# PCB_Official.net
KiCad netlist of a schematic drawn in EAGLE
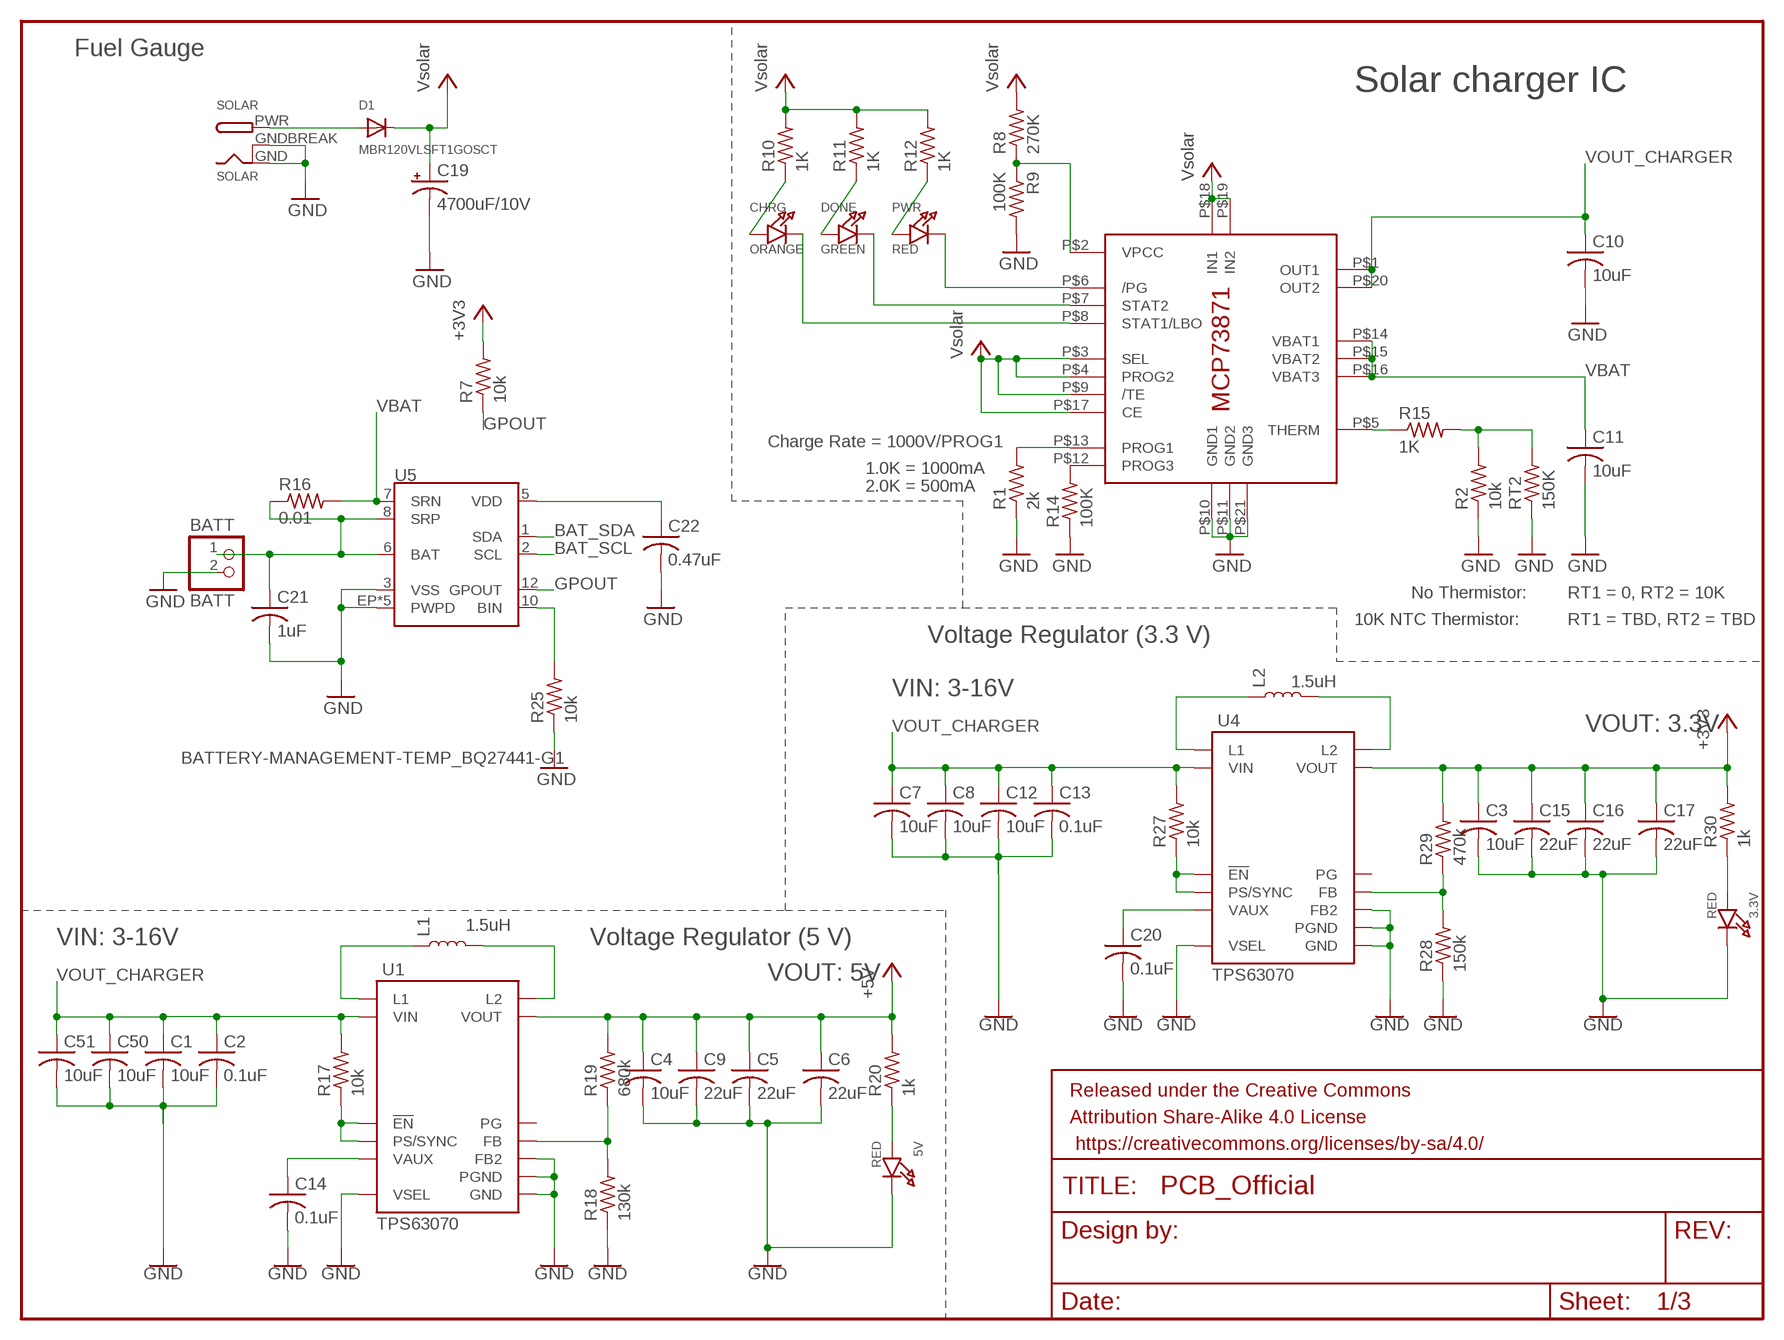
[diagram p0: schematic, sheet 1]
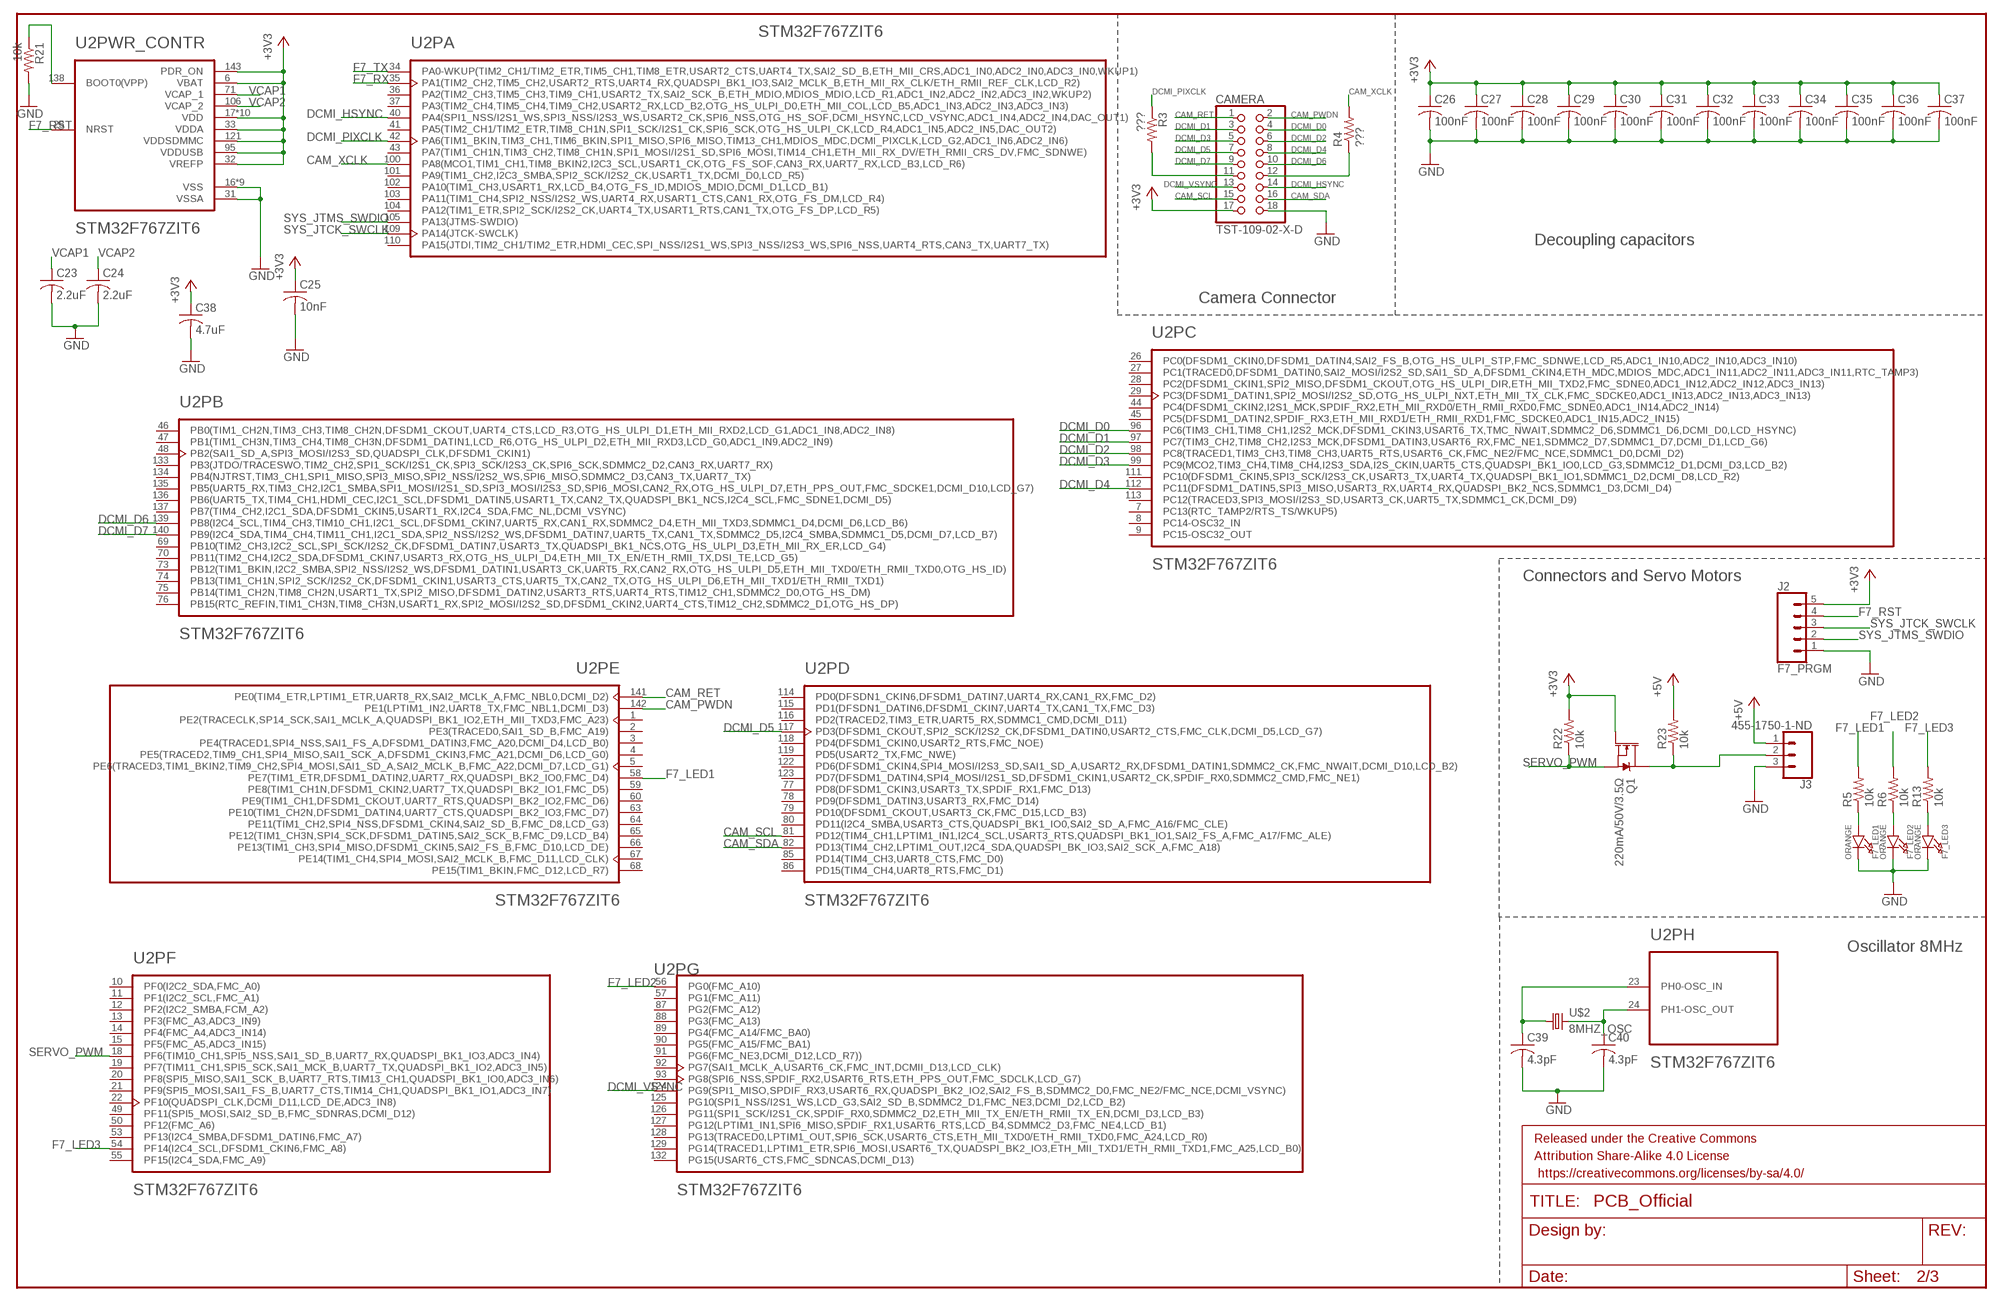
[diagram p1: schematic, sheet 2]
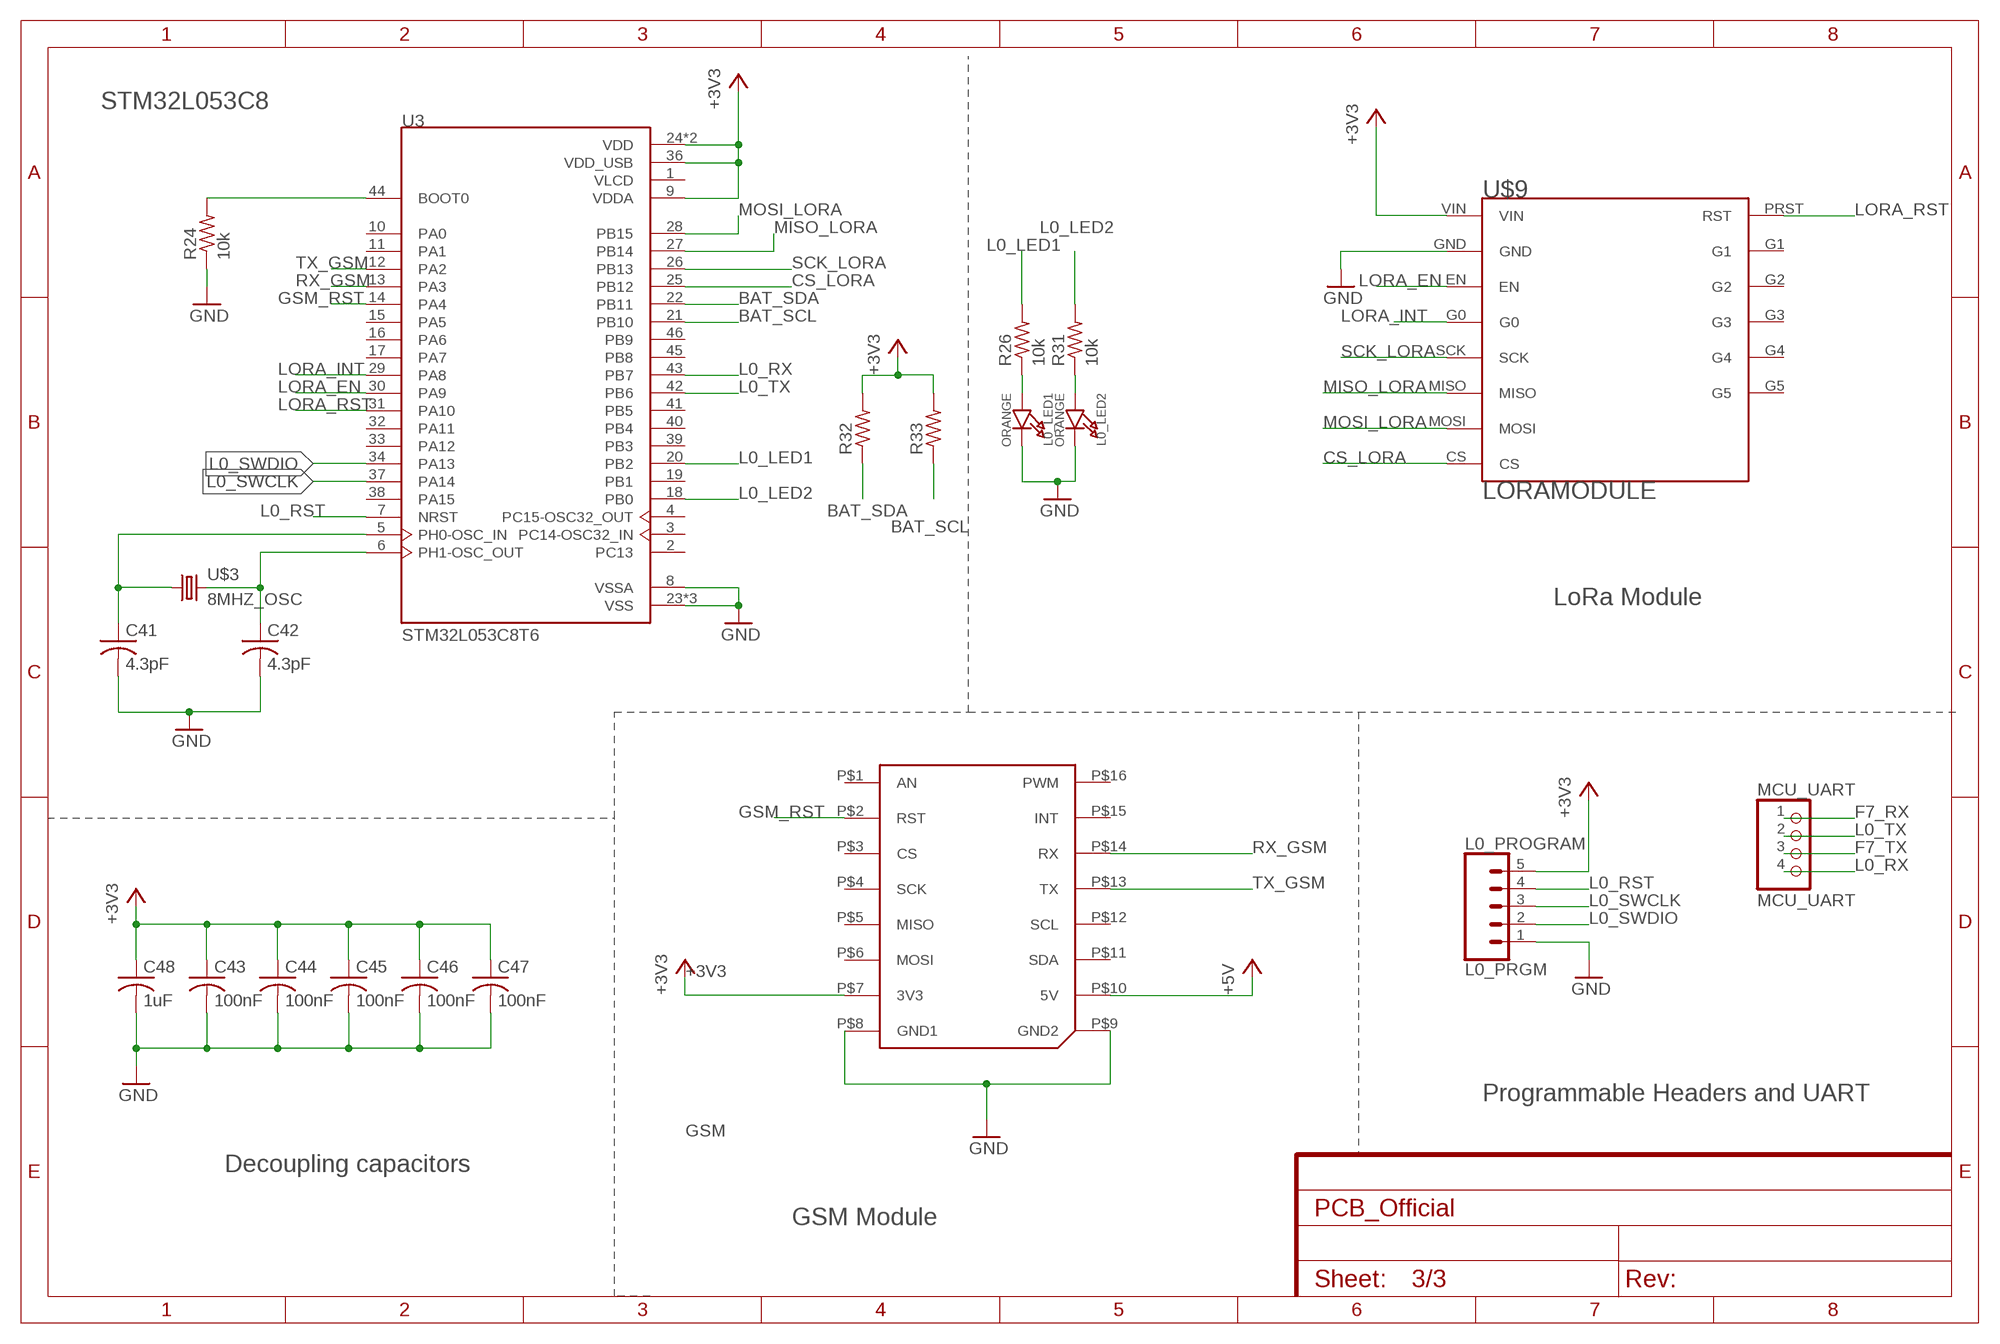
[diagram p2: schematic, sheet 3]

(export (version "E")
  (design (tool "Eeschema 10.0.6"))
  (components
    (comp (ref "C23")
      (value "2.2uF")
      (footprint "eagle-import:C0805")
      (libsource (lib "eagle-import") (part "rcl_334_C-USC0805"))
    )
    (comp (ref "C24")
      (value "2.2uF")
      (footprint "eagle-import:C0805")
      (libsource (lib "eagle-import") (part "rcl_334_C-USC0805"))
    )
    (comp (ref "C25")
      (value "10nF")
      (footprint "eagle-import:C0805")
      (libsource (lib "eagle-import") (part "rcl_334_C-USC0805"))
    )
    (comp (ref "C26")
      (value "100nF")
      (footprint "eagle-import:C0805")
      (libsource (lib "eagle-import") (part "rcl_334_C-USC0805"))
    )
    (comp (ref "C27")
      (value "100nF")
      (footprint "eagle-import:C0805")
      (libsource (lib "eagle-import") (part "rcl_334_C-USC0805"))
    )
    (comp (ref "C28")
      (value "100nF")
      (footprint "eagle-import:C0805")
      (libsource (lib "eagle-import") (part "rcl_334_C-USC0805"))
    )
    (comp (ref "C29")
      (value "100nF")
      (footprint "eagle-import:C0805")
      (libsource (lib "eagle-import") (part "rcl_334_C-USC0805"))
    )
    (comp (ref "C30")
      (value "100nF")
      (footprint "eagle-import:C0805")
      (libsource (lib "eagle-import") (part "rcl_334_C-USC0805"))
    )
    (comp (ref "C31")
      (value "100nF")
      (footprint "eagle-import:C0805")
      (libsource (lib "eagle-import") (part "rcl_334_C-USC0805"))
    )
    (comp (ref "C32")
      (value "100nF")
      (footprint "eagle-import:C0805")
      (libsource (lib "eagle-import") (part "rcl_334_C-USC0805"))
    )
    (comp (ref "C33")
      (value "100nF")
      (footprint "eagle-import:C0805")
      (libsource (lib "eagle-import") (part "rcl_334_C-USC0805"))
    )
    (comp (ref "C34")
      (value "100nF")
      (footprint "eagle-import:C0805")
      (libsource (lib "eagle-import") (part "rcl_334_C-USC0805"))
    )
    (comp (ref "C35")
      (value "100nF")
      (footprint "eagle-import:C0805")
      (libsource (lib "eagle-import") (part "rcl_334_C-USC0805"))
    )
    (comp (ref "C36")
      (value "100nF")
      (footprint "eagle-import:C0805")
      (libsource (lib "eagle-import") (part "rcl_334_C-USC0805"))
    )
    (comp (ref "C37")
      (value "100nF")
      (footprint "eagle-import:C0805")
      (libsource (lib "eagle-import") (part "rcl_334_C-USC0805"))
    )
    (comp (ref "C38")
      (value "4.7uF")
      (footprint "eagle-import:C0805")
      (libsource (lib "eagle-import") (part "rcl_334_C-USC0805"))
    )
    (comp (ref "C39")
      (value "4.3pF")
      (footprint "eagle-import:C0805")
      (libsource (lib "eagle-import") (part "rcl_334_C-USC0805"))
    )
    (comp (ref "C40")
      (value "4.3pF")
      (footprint "eagle-import:C0805")
      (libsource (lib "eagle-import") (part "rcl_334_C-USC0805"))
    )
    (comp (ref "CAMERA")
      (value "TST-109-02-X-D")
      (footprint "eagle-import:TST-109-02-X-D")
      (libsource (lib "eagle-import") (part "TST-109-02-X-D"))
    )
    (comp (ref "F7_LED1")
      (value "ORANGE")
      (footprint "eagle-import:CHIPLED_0805_NOOUTLINE")
      (libsource (lib "eagle-import") (part "LED0805_NOOUTLINE"))
    )
    (comp (ref "F7_LED2")
      (value "ORANGE")
      (footprint "eagle-import:CHIPLED_0805_NOOUTLINE")
      (libsource (lib "eagle-import") (part "LED0805_NOOUTLINE"))
    )
    (comp (ref "F7_LED3")
      (value "ORANGE")
      (footprint "eagle-import:CHIPLED_0805_NOOUTLINE")
      (libsource (lib "eagle-import") (part "LED0805_NOOUTLINE"))
    )
    (comp (ref "FRAME3")
      (value "FRAME-LEDGER")
      (footprint "eagle-import:CREATIVE_COMMONS")
      (libsource (lib "eagle-import") (part "FRAME-LEDGER"))
    )
    (comp (ref "J2")
      (value "F7_PRGM")
      (footprint "eagle-import:1X05")
      (libsource (lib "eagle-import") (part "CONN_05"))
    )
    (comp (ref "J3")
      (value "455-1750-1-ND")
      (footprint "eagle-import:1X03")
      (libsource (lib "eagle-import") (part "CONN_03"))
    )
    (comp (ref "Q1")
      (value "220mA/50V/3.5Ω")
      (footprint "eagle-import:SOT23-3")
      (libsource (lib "eagle-import") (part "MOSFET-NCH-BSS138"))
    )
    (comp (ref "R3")
      (value "???")
      (footprint "eagle-import:R0805")
      (libsource (lib "eagle-import") (part "rcl_334_R-US_R0805"))
    )
    (comp (ref "R4")
      (value "???")
      (footprint "eagle-import:R0805")
      (libsource (lib "eagle-import") (part "rcl_334_R-US_R0805"))
    )
    (comp (ref "R5")
      (value "10k")
      (footprint "eagle-import:R0805")
      (libsource (lib "eagle-import") (part "rcl_334_R-US_R0805"))
    )
    (comp (ref "R6")
      (value "10k")
      (footprint "eagle-import:R0805")
      (libsource (lib "eagle-import") (part "rcl_334_R-US_R0805"))
    )
    (comp (ref "R13")
      (value "10k")
      (footprint "eagle-import:R0805")
      (libsource (lib "eagle-import") (part "rcl_334_R-US_R0805"))
    )
    (comp (ref "R21")
      (value "10k")
      (footprint "eagle-import:R0805")
      (libsource (lib "eagle-import") (part "rcl_334_R-US_R0805"))
    )
    (comp (ref "R22")
      (value "10k")
      (footprint "eagle-import:R0805")
      (libsource (lib "eagle-import") (part "rcl_334_R-US_R0805"))
    )
    (comp (ref "R23")
      (value "10k")
      (footprint "eagle-import:R0805")
      (libsource (lib "eagle-import") (part "rcl_334_R-US_R0805"))
    )
    (comp (ref "U$2")
      (value "8MHZ_OSC")
      (footprint "eagle-import:8MHZ_OSC")
      (libsource (lib "eagle-import") (part "8MHZ_OSC"))
    )
    (comp (ref "U2")
      (value "STM32F767ZIT6")
      (footprint "eagle-import:QFP50P2200X2200X160-144N")
      (fields (field (name "DIGI-KEY_PART_NUMBER") "497-16521-ND") (field (name "MF") "STMicroelectronics"))
      (libsource (lib "eagle-import") (part "STM32F767ZIT6"))
    )
    (comp (ref "C41")
      (value "4.3pF")
      (footprint "eagle-import:C0805")
      (libsource (lib "eagle-import") (part "rcl_334_C-USC0805"))
    )
    (comp (ref "C42")
      (value "4.3pF")
      (footprint "eagle-import:C0805")
      (libsource (lib "eagle-import") (part "rcl_334_C-USC0805"))
    )
    (comp (ref "C43")
      (value "100nF")
      (footprint "eagle-import:C0805")
      (libsource (lib "eagle-import") (part "rcl_334_C-USC0805"))
    )
    (comp (ref "C44")
      (value "100nF")
      (footprint "eagle-import:C0805")
      (libsource (lib "eagle-import") (part "rcl_334_C-USC0805"))
    )
    (comp (ref "C45")
      (value "100nF")
      (footprint "eagle-import:C0805")
      (libsource (lib "eagle-import") (part "rcl_334_C-USC0805"))
    )
    (comp (ref "C46")
      (value "100nF")
      (footprint "eagle-import:C0805")
      (libsource (lib "eagle-import") (part "rcl_334_C-USC0805"))
    )
    (comp (ref "C47")
      (value "100nF")
      (footprint "eagle-import:C0805")
      (libsource (lib "eagle-import") (part "rcl_334_C-USC0805"))
    )
    (comp (ref "C48")
      (value "1uF")
      (footprint "eagle-import:C0805")
      (libsource (lib "eagle-import") (part "rcl_334_C-USC0805"))
    )
    (comp (ref "L0_LED1")
      (value "ORANGE")
      (footprint "eagle-import:CHIPLED_0805_NOOUTLINE")
      (libsource (lib "eagle-import") (part "LED0805_NOOUTLINE"))
    )
    (comp (ref "L0_LED2")
      (value "ORANGE")
      (footprint "eagle-import:CHIPLED_0805_NOOUTLINE")
      (libsource (lib "eagle-import") (part "LED0805_NOOUTLINE"))
    )
    (comp (ref "L0_PROGRAM")
      (value "L0_PRGM")
      (footprint "eagle-import:1X05")
      (libsource (lib "eagle-import") (part "CONN_05"))
    )
    (comp (ref "MCU_UART")
      (value "MCU_UART")
      (footprint "eagle-import:1X04")
      (libsource (lib "eagle-import") (part "PINHD-1X4"))
    )
    (comp (ref "R24")
      (value "10k")
      (footprint "eagle-import:R0805")
      (libsource (lib "eagle-import") (part "rcl_334_R-US_R0805"))
    )
    (comp (ref "R26")
      (value "10k")
      (footprint "eagle-import:R0805")
      (libsource (lib "eagle-import") (part "rcl_334_R-US_R0805"))
    )
    (comp (ref "R31")
      (value "10k")
      (footprint "eagle-import:R0805")
      (libsource (lib "eagle-import") (part "rcl_334_R-US_R0805"))
    )
    (comp (ref "R32")
      (value "R-US_R0805")
      (footprint "eagle-import:R0805")
      (libsource (lib "eagle-import") (part "rcl_334_R-US_R0805"))
    )
    (comp (ref "R33")
      (value "R-US_R0805")
      (footprint "eagle-import:R0805")
      (libsource (lib "eagle-import") (part "rcl_334_R-US_R0805"))
    )
    (comp (ref "U$1")
      (value "MIKROE_CLICKLARGE")
      (footprint "eagle-import:MIKROE_BUS_LARGE")
      (libsource (lib "eagle-import") (part "MIKROE_CLICKLARGE"))
    )
    (comp (ref "U$3")
      (value "8MHZ_OSC")
      (footprint "eagle-import:8MHZ_OSC")
      (libsource (lib "eagle-import") (part "8MHZ_OSC"))
    )
    (comp (ref "U$9")
      (value "LORAMODULE")
      (footprint "eagle-import:LORAMODULE")
      (libsource (lib "eagle-import") (part "LORAMODULE"))
    )
    (comp (ref "U3")
      (value "STM32L053C8T6")
      (footprint "eagle-import:QFP50P900X900X160-48N")
      (fields (field (name "DIGI-KEY_PART_NUMBER") "497-14906-ND") (field (name "MF") "STMicroelectronics"))
      (libsource (lib "eagle-import") (part "STM32L053C8T6"))
    )
    (comp (ref "3.3V")
      (value "RED")
      (footprint "eagle-import:CHIPLED_0805_NOOUTLINE")
      (libsource (lib "eagle-import") (part "LED0805_NOOUTLINE"))
    )
    (comp (ref "5V")
      (value "RED")
      (footprint "eagle-import:CHIPLED_0805_NOOUTLINE")
      (libsource (lib "eagle-import") (part "LED0805_NOOUTLINE"))
    )
    (comp (ref "BATT")
      (value "BATT")
      (footprint "eagle-import:JST-PH-2-SMT-RA")
      (libsource (lib "eagle-import") (part "JST_2PIN-SMT-RA"))
    )
    (comp (ref "C1")
      (value "10uF")
      (footprint "eagle-import:C0805")
      (libsource (lib "eagle-import") (part "C-USC0805"))
    )
    (comp (ref "C2")
      (value "0.1uF")
      (footprint "eagle-import:C0805")
      (libsource (lib "eagle-import") (part "C-USC0805"))
    )
    (comp (ref "C3")
      (value "10uF")
      (footprint "eagle-import:C0603")
      (libsource (lib "eagle-import") (part "rcl_334_C-USC0603"))
    )
    (comp (ref "C4")
      (value "10uF")
      (footprint "eagle-import:C0603")
      (libsource (lib "eagle-import") (part "rcl_334_C-USC0603"))
    )
    (comp (ref "C5")
      (value "22uF")
      (footprint "eagle-import:C0805")
      (libsource (lib "eagle-import") (part "C-USC0805"))
    )
    (comp (ref "C6")
      (value "22uF")
      (footprint "eagle-import:C0805")
      (libsource (lib "eagle-import") (part "C-USC0805"))
    )
    (comp (ref "C7")
      (value "10uF")
      (footprint "eagle-import:C0603")
      (libsource (lib "eagle-import") (part "rcl_334_C-USC0603"))
    )
    (comp (ref "C8")
      (value "10uF")
      (footprint "eagle-import:C0805")
      (libsource (lib "eagle-import") (part "C-USC0805"))
    )
    (comp (ref "C9")
      (value "22uF")
      (footprint "eagle-import:C0805")
      (libsource (lib "eagle-import") (part "C-USC0805"))
    )
    (comp (ref "C10")
      (value "10uF")
      (footprint "eagle-import:C0805K")
      (libsource (lib "eagle-import") (part "C-USC0805K"))
    )
    (comp (ref "C11")
      (value "10uF")
      (footprint "eagle-import:C0805K")
      (libsource (lib "eagle-import") (part "C-USC0805K"))
    )
    (comp (ref "C12")
      (value "10uF")
      (footprint "eagle-import:C0805")
      (libsource (lib "eagle-import") (part "C-USC0805"))
    )
    (comp (ref "C13")
      (value "0.1uF")
      (footprint "eagle-import:C0805")
      (libsource (lib "eagle-import") (part "C-USC0805"))
    )
    (comp (ref "C14")
      (value "0.1uF")
      (footprint "eagle-import:C0603")
      (libsource (lib "eagle-import") (part "rcl_334_C-USC0603"))
    )
    (comp (ref "C15")
      (value "22uF")
      (footprint "eagle-import:C0805")
      (libsource (lib "eagle-import") (part "C-USC0805"))
    )
    (comp (ref "C16")
      (value "22uF")
      (footprint "eagle-import:C0805")
      (libsource (lib "eagle-import") (part "C-USC0805"))
    )
    (comp (ref "C17")
      (value "22uF")
      (footprint "eagle-import:C0805")
      (libsource (lib "eagle-import") (part "C-USC0805"))
    )
    (comp (ref "C19")
      (value "4700uF/10V")
      (footprint "eagle-import:ADAFRUIT_E5-13")
      (libsource (lib "eagle-import") (part "ADAFRUIT_CPOL-USE5-13"))
    )
    (comp (ref "C20")
      (value "0.1uF")
      (footprint "eagle-import:C0603")
      (libsource (lib "eagle-import") (part "rcl_334_C-USC0603"))
    )
    (comp (ref "C21")
      (value "1uF")
      (footprint "eagle-import:C0805")
      (libsource (lib "eagle-import") (part "rcl_334_C-USC0805"))
    )
    (comp (ref "C22")
      (value "0.47uF")
      (footprint "eagle-import:C0805")
      (libsource (lib "eagle-import") (part "rcl_334_C-USC0805"))
    )
    (comp (ref "C50")
      (value "10uF")
      (footprint "eagle-import:C0805")
      (libsource (lib "eagle-import") (part "C-USC0805"))
    )
    (comp (ref "C51")
      (value "10uF")
      (footprint "eagle-import:C0603")
      (libsource (lib "eagle-import") (part "rcl_334_C-USC0603"))
    )
    (comp (ref "CHRG")
      (value "ORANGE")
      (footprint "eagle-import:CHIPLED_0805_NOOUTLINE")
      (libsource (lib "eagle-import") (part "LED0805_NOOUTLINE"))
    )
    (comp (ref "D1")
      (value "MBR120VLSFT1GOSCT")
      (footprint "eagle-import:MICROBUILDER_SOD-123")
      (libsource (lib "eagle-import") (part "MICROBUILDER_DIODESOD-123"))
    )
    (comp (ref "DONE")
      (value "GREEN")
      (footprint "eagle-import:CHIPLED_0805_NOOUTLINE")
      (libsource (lib "eagle-import") (part "LED0805_NOOUTLINE"))
    )
    (comp (ref "FRAME2")
      (value "FRAME-LETTERNO_PACKAGE")
      (footprint "eagle-import:DUMMY")
      (fields (field (name "DESIGNER") "Nobody"))
      (libsource (lib "eagle-import") (part "FRAME-LETTERNO_PACKAGE"))
    )
    (comp (ref "IC1")
      (value "MCP73871")
      (footprint "eagle-import:QFN20_4MM")
      (libsource (lib "eagle-import") (part "MCP73871"))
    )
    (comp (ref "L1")
      (value "1.5uH")
      (footprint "eagle-import:XFL4020")
      (libsource (lib "eagle-import") (part "INDUCTOR-XFL40201.5UH"))
    )
    (comp (ref "L2")
      (value "1.5uH")
      (footprint "eagle-import:XFL4020")
      (libsource (lib "eagle-import") (part "INDUCTOR-XFL40201.5UH"))
    )
    (comp (ref "PWR")
      (value "RED")
      (footprint "eagle-import:CHIPLED_0805_NOOUTLINE")
      (libsource (lib "eagle-import") (part "LED0805_NOOUTLINE"))
    )
    (comp (ref "R1")
      (value "2k")
      (footprint "eagle-import:R0805")
      (libsource (lib "eagle-import") (part "adafruit_420_R-US_R0805"))
    )
    (comp (ref "R2")
      (value "10k")
      (footprint "eagle-import:R0805")
      (libsource (lib "eagle-import") (part "adafruit_420_R-US_R0805"))
    )
    (comp (ref "R7")
      (value "10k")
      (footprint "eagle-import:R0805")
      (libsource (lib "eagle-import") (part "adafruit_420_R-US_R0805"))
    )
    (comp (ref "R8")
      (value "270K")
      (footprint "eagle-import:R0805")
      (libsource (lib "eagle-import") (part "R-US_R0805"))
    )
    (comp (ref "R9")
      (value "100K")
      (footprint "eagle-import:R0805")
      (libsource (lib "eagle-import") (part "R-US_R0805"))
    )
    (comp (ref "R10")
      (value "1K")
      (footprint "eagle-import:R0805")
      (libsource (lib "eagle-import") (part "R-US_R0805"))
    )
    (comp (ref "R11")
      (value "1K")
      (footprint "eagle-import:R0805")
      (libsource (lib "eagle-import") (part "R-US_R0805"))
    )
    (comp (ref "R12")
      (value "1K")
      (footprint "eagle-import:R0805")
      (libsource (lib "eagle-import") (part "R-US_R0805"))
    )
    (comp (ref "R14")
      (value "100K")
      (footprint "eagle-import:R0805")
      (libsource (lib "eagle-import") (part "R-US_R0805"))
    )
    (comp (ref "R15")
      (value "1K")
      (footprint "eagle-import:M0805")
      (libsource (lib "eagle-import") (part "R-US_M0805"))
    )
    (comp (ref "R16")
      (value "0.01")
      (footprint "eagle-import:R0805")
      (libsource (lib "eagle-import") (part "rcl_334_R-US_R0805"))
    )
    (comp (ref "R17")
      (value "10k")
      (footprint "eagle-import:R0603")
      (libsource (lib "eagle-import") (part "rcl_334_R-US_R0603"))
    )
    (comp (ref "R18")
      (value "130k")
      (footprint "eagle-import:R0603")
      (libsource (lib "eagle-import") (part "rcl_334_R-US_R0603"))
    )
    (comp (ref "R19")
      (value "680k")
      (footprint "eagle-import:R0603")
      (libsource (lib "eagle-import") (part "rcl_334_R-US_R0603"))
    )
    (comp (ref "R20")
      (value "1k")
      (footprint "eagle-import:R0603")
      (libsource (lib "eagle-import") (part "rcl_334_R-US_R0603"))
    )
    (comp (ref "R25")
      (value "10k")
      (footprint "eagle-import:R0805")
      (libsource (lib "eagle-import") (part "adafruit_420_R-US_R0805"))
    )
    (comp (ref "R27")
      (value "10k")
      (footprint "eagle-import:R0603")
      (libsource (lib "eagle-import") (part "rcl_334_R-US_R0603"))
    )
    (comp (ref "R28")
      (value "150k")
      (footprint "eagle-import:R0603")
      (libsource (lib "eagle-import") (part "rcl_334_R-US_R0603"))
    )
    (comp (ref "R29")
      (value "470k")
      (footprint "eagle-import:R0603")
      (libsource (lib "eagle-import") (part "rcl_334_R-US_R0603"))
    )
    (comp (ref "R30")
      (value "1k")
      (footprint "eagle-import:R0603")
      (libsource (lib "eagle-import") (part "rcl_334_R-US_R0603"))
    )
    (comp (ref "RT2")
      (value "150K")
      (footprint "eagle-import:M0805")
      (libsource (lib "eagle-import") (part "R-US_M0805"))
    )
    (comp (ref "SOLAR")
      (value "SOLAR")
      (footprint "eagle-import:DCJACK_2MM_PTH")
      (libsource (lib "eagle-import") (part "DCBARRELPTH"))
    )
    (comp (ref "U1")
      (value "TPS63070")
      (footprint "eagle-import:VQFN-15-HR(3X2.5)")
      (libsource (lib "eagle-import") (part "TPS63070"))
    )
    (comp (ref "U4")
      (value "TPS63070")
      (footprint "eagle-import:VQFN-15-HR(3X2.5)")
      (libsource (lib "eagle-import") (part "TPS63070"))
    )
    (comp (ref "U5")
      (value "BATTERY-MANAGEMENT-TEMP_BQ27441-G1")
      (footprint "eagle-import:BATTERY-MANAGEMENT-TEMP_PDSO-N12")
      (libsource (lib "eagle-import") (part "BATTERY-MANAGEMENT-TEMP_BQ27441-G1"))
    )
  )
  (nets
    (net (code "1") (name "+3V3") (class "Default")
      (node (ref "C15") (pin "1") (pinfunction "1_1") (pintype "passive"))
      (node (ref "C16") (pin "1") (pinfunction "1_1") (pintype "passive"))
      (node (ref "C17") (pin "1") (pinfunction "1_1") (pintype "passive"))
      (node (ref "C25") (pin "1") (pinfunction "1_1") (pintype "passive"))
      (node (ref "C26") (pin "1") (pinfunction "1_1") (pintype "passive"))
      (node (ref "C27") (pin "1") (pinfunction "1_1") (pintype "passive"))
      (node (ref "C28") (pin "1") (pinfunction "1_1") (pintype "passive"))
      (node (ref "C29") (pin "1") (pinfunction "1_1") (pintype "passive"))
      (node (ref "C3") (pin "1") (pinfunction "1_1") (pintype "passive"))
      (node (ref "C30") (pin "1") (pinfunction "1_1") (pintype "passive"))
      (node (ref "C31") (pin "1") (pinfunction "1_1") (pintype "passive"))
      (node (ref "C32") (pin "1") (pinfunction "1_1") (pintype "passive"))
      (node (ref "C33") (pin "1") (pinfunction "1_1") (pintype "passive"))
      (node (ref "C34") (pin "1") (pinfunction "1_1") (pintype "passive"))
      (node (ref "C35") (pin "1") (pinfunction "1_1") (pintype "passive"))
      (node (ref "C36") (pin "1") (pinfunction "1_1") (pintype "passive"))
      (node (ref "C37") (pin "1") (pinfunction "1_1") (pintype "passive"))
      (node (ref "C38") (pin "1") (pinfunction "1_1") (pintype "passive"))
      (node (ref "C43") (pin "1") (pinfunction "1_1") (pintype "passive"))
      (node (ref "C44") (pin "1") (pinfunction "1_1") (pintype "passive"))
      (node (ref "C45") (pin "1") (pinfunction "1_1") (pintype "passive"))
      (node (ref "C46") (pin "1") (pinfunction "1_1") (pintype "passive"))
      (node (ref "C47") (pin "1") (pinfunction "1_1") (pintype "passive"))
      (node (ref "C48") (pin "1") (pinfunction "1_1") (pintype "passive"))
      (node (ref "CAMERA") (pin "17") (pinfunction "17_17") (pintype "passive"))
      (node (ref "J2") (pin "5") (pinfunction "5_5") (pintype "passive"))
      (node (ref "L0_PROGRAM") (pin "5") (pinfunction "5_5") (pintype "passive"))
      (node (ref "Q1") (pin "1") (pinfunction "G_1") (pintype "bidirectional"))
      (node (ref "R22") (pin "2") (pinfunction "2_2") (pintype "passive"))
      (node (ref "R29") (pin "2") (pinfunction "2_2") (pintype "passive"))
      (node (ref "R30") (pin "2") (pinfunction "2_2") (pintype "passive"))
      (node (ref "R32") (pin "2") (pinfunction "2_2") (pintype "passive"))
      (node (ref "R33") (pin "2") (pinfunction "2_2") (pintype "passive"))
      (node (ref "R7") (pin "2") (pinfunction "2_2") (pintype "passive"))
      (node (ref "U$1") (pin "P$7") (pinfunction "3V3_P$7") (pintype "bidirectional"))
      (node (ref "U$9") (pin "VIN") (pinfunction "VIN_VIN") (pintype "power_in"))
      (node (ref "U2") (pin "108") (pinfunction "VDD_108") (pintype "power_in"))
      (node (ref "U2") (pin "121") (pinfunction "VDDSDMMC_121") (pintype "power_in"))
      (node (ref "U2") (pin "131") (pinfunction "VDD_131") (pintype "power_in"))
      (node (ref "U2") (pin "143") (pinfunction "PDR_ON_143") (pintype "power_in"))
      (node (ref "U2") (pin "144") (pinfunction "VDD_144") (pintype "power_in"))
      (node (ref "U2") (pin "17") (pinfunction "VDD_17") (pintype "power_in"))
      (node (ref "U2") (pin "30") (pinfunction "VDD_30") (pintype "power_in"))
      (node (ref "U2") (pin "32") (pinfunction "VREFP_32") (pintype "power_in"))
      (node (ref "U2") (pin "33") (pinfunction "VDDA_33") (pintype "power_in"))
      (node (ref "U2") (pin "39") (pinfunction "VDD_39") (pintype "power_in"))
      (node (ref "U2") (pin "52") (pinfunction "VDD_52") (pintype "power_in"))
      (node (ref "U2") (pin "6") (pinfunction "VBAT_6") (pintype "power_in"))
      (node (ref "U2") (pin "62") (pinfunction "VDD_62") (pintype "power_in"))
      (node (ref "U2") (pin "72") (pinfunction "VDD_72") (pintype "power_in"))
      (node (ref "U2") (pin "84") (pinfunction "VDD_84") (pintype "power_in"))
      (node (ref "U2") (pin "95") (pinfunction "VDDUSB_95") (pintype "power_in"))
      (node (ref "U3") (pin "24") (pinfunction "VDD_24") (pintype "bidirectional"))
      (node (ref "U3") (pin "36") (pinfunction "VDD_USB_36") (pintype "bidirectional"))
      (node (ref "U3") (pin "48") (pinfunction "VDD_48") (pintype "bidirectional"))
      (node (ref "U3") (pin "9") (pinfunction "VDDA_9") (pintype "bidirectional"))
      (node (ref "U4") (pin "P$7/8") (pinfunction "VOUT_P$7/8") (pintype "bidirectional"))
    )
    (net (code "2") (name "+5V") (class "Default")
      (node (ref "C4") (pin "1") (pinfunction "1_1") (pintype "passive"))
      (node (ref "C5") (pin "1") (pinfunction "1_1") (pintype "passive"))
      (node (ref "C6") (pin "1") (pinfunction "1_1") (pintype "passive"))
      (node (ref "C9") (pin "1") (pinfunction "1_1") (pintype "passive"))
      (node (ref "J3") (pin "1") (pinfunction "1_1") (pintype "passive"))
      (node (ref "R19") (pin "2") (pinfunction "2_2") (pintype "passive"))
      (node (ref "R20") (pin "2") (pinfunction "2_2") (pintype "passive"))
      (node (ref "R23") (pin "2") (pinfunction "2_2") (pintype "passive"))
      (node (ref "U$1") (pin "P$10") (pinfunction "5V_P$10") (pintype "bidirectional"))
      (node (ref "U1") (pin "P$7/8") (pinfunction "VOUT_P$7/8") (pintype "bidirectional"))
    )
    (net (code "3") (name "BAT_SCL") (class "Default")
      (node (ref "R33") (pin "1") (pinfunction "1_1") (pintype "passive"))
      (node (ref "U3") (pin "21") (pinfunction "PB10_21") (pintype "bidirectional"))
      (node (ref "U5") (pin "2") (pinfunction "SCL_2") (pintype "bidirectional"))
    )
    (net (code "4") (name "BAT_SDA") (class "Default")
      (node (ref "R32") (pin "1") (pinfunction "1_1") (pintype "passive"))
      (node (ref "U3") (pin "22") (pinfunction "PB11_22") (pintype "bidirectional"))
      (node (ref "U5") (pin "1") (pinfunction "SDA_1") (pintype "bidirectional"))
    )
    (net (code "5") (name "CAM_PWDN") (class "Default")
      (node (ref "CAMERA") (pin "2") (pinfunction "2_2") (pintype "passive"))
      (node (ref "U2") (pin "142") (pinfunction "PE1(LPTIM1_IN2,UART8_TX,FMC_NBL1,DCMI_D3)_142") (pintype "bidirectional"))
    )
    (net (code "6") (name "CAM_RET") (class "Default")
      (node (ref "CAMERA") (pin "1") (pinfunction "1_1") (pintype "passive"))
      (node (ref "U2") (pin "141") (pinfunction "PE0(TIM4_ETR,LPTIM1_ETR,UART8_RX,SAI2_MCLK_A,FMC_NBL0,DCMI_D2)_141") (pintype "bidirectional"))
    )
    (net (code "7") (name "CAM_SCL") (class "Default")
      (node (ref "CAMERA") (pin "15") (pinfunction "15_15") (pintype "passive"))
      (node (ref "U2") (pin "81") (pinfunction "PD12(TIM4_CH1,LPTIM1_IN1,I2C4_SCL,USART3_RTS,QUADSPI_BK1_IO1,SAI2_FS_A,FMC_A17/FMC_ALE)_81") (pintype "bidirectional"))
    )
    (net (code "8") (name "CAM_SDA") (class "Default")
      (node (ref "CAMERA") (pin "16") (pinfunction "16_16") (pintype "passive"))
      (node (ref "U2") (pin "82") (pinfunction "PD13(TIM4_CH2,LPTIM1_OUT,I2C4_SDA,QUADSPI_BK_IO3,SAI2_SCK_A,FMC_A18)_82") (pintype "bidirectional"))
    )
    (net (code "9") (name "CAM_XCLK") (class "Default")
      (node (ref "R4") (pin "2") (pinfunction "2_2") (pintype "passive"))
      (node (ref "U2") (pin "100") (pinfunction "PA8(MCO1,TIM1_CH1,TIM8_BKIN2,I2C3_SCL,USART1_CK,OTG_FS_SOF,CAN3_RX,UART7_RX,LCD_B3,LCD_R6)_100") (pintype "bidirectional"))
    )
    (net (code "10") (name "CS_LORA") (class "Default")
      (node (ref "U$9") (pin "CS") (pinfunction "CS_CS") (pintype "bidirectional"))
      (node (ref "U3") (pin "25") (pinfunction "PB12_25") (pintype "bidirectional"))
    )
    (net (code "11") (name "DCMI_D0") (class "Default")
      (node (ref "CAMERA") (pin "4") (pinfunction "4_4") (pintype "passive"))
      (node (ref "U2") (pin "96") (pinfunction "PC6(TIM3_CH1,TIM8_CH1,I2S2_MCK,DFSDM1_CKIN3,USART6_TX,TMC_NWAIT,SDMMC2_D6,SDMMC1_D6,DCMI_D0,LCD_HSYNC)_96") (pintype "bidirectional"))
    )
    (net (code "12") (name "DCMI_D1") (class "Default")
      (node (ref "CAMERA") (pin "3") (pinfunction "3_3") (pintype "passive"))
      (node (ref "U2") (pin "97") (pinfunction "PC7(TIM3_CH2,TIM8_CH2,I2S3_MCK,DFSDM1_DATIN3,USART6_RX,FMC_NE1,SDMMC2_D7,SDMMC1_D7,DCMI_D1,LCD_G6)_97") (pintype "bidirectional"))
    )
    (net (code "13") (name "DCMI_D2") (class "Default")
      (node (ref "CAMERA") (pin "6") (pinfunction "6_6") (pintype "passive"))
      (node (ref "U2") (pin "98") (pinfunction "PC8(TRACED1,TIM3_CH3,TIM8_CH3,UART5_RTS,USART6_CK,FMC_NE2/FMC_NCE,SDMMC1_D0,DCMI_D2)_98") (pintype "bidirectional"))
    )
    (net (code "14") (name "DCMI_D3") (class "Default")
      (node (ref "CAMERA") (pin "5") (pinfunction "5_5") (pintype "passive"))
      (node (ref "U2") (pin "99") (pinfunction "PC9(MCO2,TIM3_CH4,TIM8_CH4,I2S3_SDA,I2S_CKIN,UART5_CTS,QUADSPI_BK1_IO0,LCD_G3,SDMMC12_D1,DCMI_D3,LCD_B2)_99") (pintype "bidirectional"))
    )
    (net (code "15") (name "DCMI_D4") (class "Default")
      (node (ref "CAMERA") (pin "8") (pinfunction "8_8") (pintype "passive"))
      (node (ref "U2") (pin "112") (pinfunction "PC11(DFSDM1_DATIN5,SPI3_MISO,USART3_RX,UART4_RX,QUADSPI_BK2_NCS,SDMMC1_D3,DCMI_D4)_112") (pintype "bidirectional"))
    )
    (net (code "16") (name "DCMI_D5") (class "Default")
      (node (ref "CAMERA") (pin "7") (pinfunction "7_7") (pintype "passive"))
      (node (ref "U2") (pin "117") (pinfunction "PD3(DFSDM1_CKOUT,SPI2_SCK/I2S2_CK,DFSDM1_DATIN0,USART2_CTS,FMC_CLK,DCMI_D5,LCD_G7)_117") (pintype "bidirectional"))
    )
    (net (code "17") (name "DCMI_D6") (class "Default")
      (node (ref "CAMERA") (pin "10") (pinfunction "10_10") (pintype "passive"))
      (node (ref "U2") (pin "139") (pinfunction "PB8(I2C4_SCL,TIM4_CH3,TIM10_CH1,I2C1_SCL,DFSDM1_CKIN7,UART5_RX,CAN1_RX,SDMMC2_D4,ETH_MII_TXD3,SDMMC1_D4,DCMI_D6,LCD_B6)_139") (pintype "bidirectional"))
    )
    (net (code "18") (name "DCMI_D7") (class "Default")
      (node (ref "CAMERA") (pin "9") (pinfunction "9_9") (pintype "passive"))
      (node (ref "U2") (pin "140") (pinfunction "PB9(I2C4_SDA,TIM4_CH4,TIM11_CH1,I2C1_SDA,SPI2_NSS/I2S2_WS,DFSDM1_DATIN7,UART5_TX,CAN1_TX,SDMMC2_D5,I2C4_SMBA,SDMMC1_D5,DCMI_D7,LCD_B7)_140") (pintype "bidirectional"))
    )
    (net (code "19") (name "DCMI_HSYNC") (class "Default")
      (node (ref "CAMERA") (pin "14") (pinfunction "14_14") (pintype "passive"))
      (node (ref "U2") (pin "40") (pinfunction "PA4(SPI1_NSS/I2S1_WS,SPI3_NSS/I2S3_WS,USART2_CK,SPI6_NSS,OTG_HS_SOF,DCMI_HSYNC,LCD_VSYNC,ADC1_IN4,ADC2_IN4,DAC_OUT1)_40") (pintype "bidirectional"))
    )
    (net (code "20") (name "DCMI_PIXCLK") (class "Default")
      (node (ref "R3") (pin "1") (pinfunction "1_1") (pintype "passive"))
      (node (ref "U2") (pin "42") (pinfunction "PA6(TIM1_BKIN,TIM3_CH1,TIM6_BKIN,SPI1_MISO,SPI6_MISO,TIM13_CH1,MDIOS_MDC,DCMI_PIXCLK,LCD_G2,ADC1_IN6,ADC2_IN6)_42") (pintype "bidirectional"))
    )
    (net (code "21") (name "DCMI_VSYNC") (class "Default")
      (node (ref "CAMERA") (pin "13") (pinfunction "13_13") (pintype "passive"))
      (node (ref "U2") (pin "124") (pinfunction "PG9(SPI1_MISO,SPDIF_RX3,USART6_RX,QUADSPI_BK2_IO2,SAI2_FS_B,SDMMC2_D0,FMC_NE2/FMC_NCE,DCMI_VSYNC)_124") (pintype "bidirectional"))
    )
    (net (code "22") (name "F7_LED1") (class "Default")
      (node (ref "R5") (pin "2") (pinfunction "2_2") (pintype "passive"))
      (node (ref "U2") (pin "58") (pinfunction "PE7(TIM1_ETR,DFSDM1_DATIN2,UART7_RX,QUADSPI_BK2_IO0,FMC_D4)_58") (pintype "bidirectional"))
    )
    (net (code "23") (name "F7_LED2") (class "Default")
      (node (ref "R6") (pin "2") (pinfunction "2_2") (pintype "passive"))
      (node (ref "U2") (pin "56") (pinfunction "PG0(FMC_A10)_56") (pintype "bidirectional"))
    )
    (net (code "24") (name "F7_LED3") (class "Default")
      (node (ref "R13") (pin "2") (pinfunction "2_2") (pintype "passive"))
      (node (ref "U2") (pin "54") (pinfunction "PF14(I2C4_SCL,DFSDM1_CKIN6,FMC_A8)_54") (pintype "bidirectional"))
    )
    (net (code "25") (name "F7_RST") (class "Default")
      (node (ref "J2") (pin "4") (pinfunction "4_4") (pintype "passive"))
      (node (ref "U2") (pin "25") (pinfunction "NRST_25") (pintype "bidirectional"))
    )
    (net (code "26") (name "F7_RX") (class "Default")
      (node (ref "MCU_UART") (pin "1") (pinfunction "1_1") (pintype "passive"))
      (node (ref "U2") (pin "35") (pinfunction "PA1(TIM2_CH2,TIM5_CH2,USART2_RTS,UART4_RX,QUADSPI_BK1_IO3,SAI2_MCLK_B,ETH_MII_RX_CLK/ETH_RMII_REF_CLK,LCD_R2)_35") (pintype "bidirectional"))
    )
    (net (code "27") (name "F7_TX") (class "Default")
      (node (ref "MCU_UART") (pin "3") (pinfunction "3_3") (pintype "passive"))
      (node (ref "U2") (pin "34") (pinfunction "PA0-WKUP(TIM2_CH1/TIM2_ETR,TIM5_CH1,TIM8_ETR,USART2_CTS,UART4_TX,SAI2_SD_B,ETH_MII_CRS,ADC1_IN0,ADC2_IN0,ADC3_IN0,WKUP1)_34") (pintype "bidirectional"))
    )
    (net (code "28") (name "GND") (class "Default")
      (node (ref "3.3V") (pin "C") (pinfunction "C_C") (pintype "passive"))
      (node (ref "5V") (pin "C") (pinfunction "C_C") (pintype "passive"))
      (node (ref "BATT") (pin "2") (pinfunction "1_2") (pintype "passive"))
      (node (ref "C1") (pin "2") (pinfunction "2_2") (pintype "passive"))
      (node (ref "C10") (pin "2") (pinfunction "2_2") (pintype "passive"))
      (node (ref "C11") (pin "2") (pinfunction "2_2") (pintype "passive"))
      (node (ref "C12") (pin "2") (pinfunction "2_2") (pintype "passive"))
      (node (ref "C13") (pin "2") (pinfunction "2_2") (pintype "passive"))
      (node (ref "C14") (pin "2") (pinfunction "2_2") (pintype "passive"))
      (node (ref "C15") (pin "2") (pinfunction "2_2") (pintype "passive"))
      (node (ref "C16") (pin "2") (pinfunction "2_2") (pintype "passive"))
      (node (ref "C17") (pin "2") (pinfunction "2_2") (pintype "passive"))
      (node (ref "C19") (pin "-") (pinfunction "-_-") (pintype "passive"))
      (node (ref "C2") (pin "2") (pinfunction "2_2") (pintype "passive"))
      (node (ref "C20") (pin "2") (pinfunction "2_2") (pintype "passive"))
      (node (ref "C21") (pin "2") (pinfunction "2_2") (pintype "passive"))
      (node (ref "C22") (pin "2") (pinfunction "2_2") (pintype "passive"))
      (node (ref "C23") (pin "2") (pinfunction "2_2") (pintype "passive"))
      (node (ref "C24") (pin "2") (pinfunction "2_2") (pintype "passive"))
      (node (ref "C25") (pin "2") (pinfunction "2_2") (pintype "passive"))
      (node (ref "C26") (pin "2") (pinfunction "2_2") (pintype "passive"))
      (node (ref "C27") (pin "2") (pinfunction "2_2") (pintype "passive"))
      (node (ref "C28") (pin "2") (pinfunction "2_2") (pintype "passive"))
      (node (ref "C29") (pin "2") (pinfunction "2_2") (pintype "passive"))
      (node (ref "C3") (pin "2") (pinfunction "2_2") (pintype "passive"))
      (node (ref "C30") (pin "2") (pinfunction "2_2") (pintype "passive"))
      (node (ref "C31") (pin "2") (pinfunction "2_2") (pintype "passive"))
      (node (ref "C32") (pin "2") (pinfunction "2_2") (pintype "passive"))
      (node (ref "C33") (pin "2") (pinfunction "2_2") (pintype "passive"))
      (node (ref "C34") (pin "2") (pinfunction "2_2") (pintype "passive"))
      (node (ref "C35") (pin "2") (pinfunction "2_2") (pintype "passive"))
      (node (ref "C36") (pin "2") (pinfunction "2_2") (pintype "passive"))
      (node (ref "C37") (pin "2") (pinfunction "2_2") (pintype "passive"))
      (node (ref "C38") (pin "2") (pinfunction "2_2") (pintype "passive"))
      (node (ref "C39") (pin "2") (pinfunction "2_2") (pintype "passive"))
      (node (ref "C4") (pin "2") (pinfunction "2_2") (pintype "passive"))
      (node (ref "C40") (pin "2") (pinfunction "2_2") (pintype "passive"))
      (node (ref "C41") (pin "2") (pinfunction "2_2") (pintype "passive"))
      (node (ref "C42") (pin "2") (pinfunction "2_2") (pintype "passive"))
      (node (ref "C43") (pin "2") (pinfunction "2_2") (pintype "passive"))
      (node (ref "C44") (pin "2") (pinfunction "2_2") (pintype "passive"))
      (node (ref "C45") (pin "2") (pinfunction "2_2") (pintype "passive"))
      (node (ref "C46") (pin "2") (pinfunction "2_2") (pintype "passive"))
      (node (ref "C47") (pin "2") (pinfunction "2_2") (pintype "passive"))
      (node (ref "C48") (pin "2") (pinfunction "2_2") (pintype "passive"))
      (node (ref "C5") (pin "2") (pinfunction "2_2") (pintype "passive"))
      (node (ref "C50") (pin "2") (pinfunction "2_2") (pintype "passive"))
      (node (ref "C51") (pin "2") (pinfunction "2_2") (pintype "passive"))
      (node (ref "C6") (pin "2") (pinfunction "2_2") (pintype "passive"))
      (node (ref "C7") (pin "2") (pinfunction "2_2") (pintype "passive"))
      (node (ref "C8") (pin "2") (pinfunction "2_2") (pintype "passive"))
      (node (ref "C9") (pin "2") (pinfunction "2_2") (pintype "passive"))
      (node (ref "CAMERA") (pin "18") (pinfunction "18_18") (pintype "passive"))
      (node (ref "F7_LED1") (pin "C") (pinfunction "C_C") (pintype "passive"))
      (node (ref "F7_LED2") (pin "C") (pinfunction "C_C") (pintype "passive"))
      (node (ref "F7_LED3") (pin "C") (pinfunction "C_C") (pintype "passive"))
      (node (ref "IC1") (pin "P$10") (pinfunction "GND1_P$10") (pintype "power_in"))
      (node (ref "IC1") (pin "P$11") (pinfunction "GND2_P$11") (pintype "power_in"))
      (node (ref "IC1") (pin "P$21") (pinfunction "GND3_P$21") (pintype "power_in"))
      (node (ref "J2") (pin "1") (pinfunction "1_1") (pintype "passive"))
      (node (ref "J3") (pin "3") (pinfunction "3_3") (pintype "passive"))
      (node (ref "L0_LED1") (pin "C") (pinfunction "C_C") (pintype "passive"))
      (node (ref "L0_LED2") (pin "C") (pinfunction "C_C") (pintype "passive"))
      (node (ref "L0_PROGRAM") (pin "1") (pinfunction "1_1") (pintype "passive"))
      (node (ref "R1") (pin "1") (pinfunction "1_1") (pintype "passive"))
      (node (ref "R14") (pin "1") (pinfunction "1_1") (pintype "passive"))
      (node (ref "R18") (pin "1") (pinfunction "1_1") (pintype "passive"))
      (node (ref "R2") (pin "1") (pinfunction "1_1") (pintype "passive"))
      (node (ref "R21") (pin "2") (pinfunction "2_2") (pintype "passive"))
      (node (ref "R24") (pin "1") (pinfunction "1_1") (pintype "passive"))
      (node (ref "R25") (pin "1") (pinfunction "1_1") (pintype "passive"))
      (node (ref "R28") (pin "1") (pinfunction "1_1") (pintype "passive"))
      (node (ref "R9") (pin "2") (pinfunction "2_2") (pintype "passive"))
      (node (ref "RT2") (pin "1") (pinfunction "1_1") (pintype "passive"))
      (node (ref "SOLAR") (pin "GND") (pinfunction "GND_GND") (pintype "power_in"))
      (node (ref "SOLAR") (pin "GNDBREAK") (pinfunction "GNDBREAK_GNDBREAK") (pintype "power_in"))
      (node (ref "U$1") (pin "P$8") (pinfunction "GND1_P$8") (pintype "bidirectional"))
      (node (ref "U$1") (pin "P$9") (pinfunction "GND2_P$9") (pintype "bidirectional"))
      (node (ref "U$9") (pin "GND") (pinfunction "GND_GND") (pintype "power_in"))
      (node (ref "U1") (pin "P$10") (pinfunction "PGND_P$10") (pintype "bidirectional"))
      (node (ref "U1") (pin "P$15") (pinfunction "VSEL_P$15") (pintype "bidirectional"))
      (node (ref "U1") (pin "P$4") (pinfunction "GND_P$4") (pintype "bidirectional"))
      (node (ref "U1") (pin "P$6") (pinfunction "FB2_P$6") (pintype "bidirectional"))
      (node (ref "U2") (pin "107") (pinfunction "VSS_107") (pintype "power_in"))
      (node (ref "U2") (pin "120") (pinfunction "VSS_120") (pintype "power_in"))
      (node (ref "U2") (pin "130") (pinfunction "VSS_130") (pintype "power_in"))
      (node (ref "U2") (pin "16") (pinfunction "VSS_16") (pintype "power_in"))
      (node (ref "U2") (pin "31") (pinfunction "VSSA_31") (pintype "power_in"))
      (node (ref "U2") (pin "38") (pinfunction "VSS_38") (pintype "power_in"))
      (node (ref "U2") (pin "51") (pinfunction "VSS_51") (pintype "power_in"))
      (node (ref "U2") (pin "61") (pinfunction "VSS_61") (pintype "power_in"))
      (node (ref "U2") (pin "83") (pinfunction "VSS_83") (pintype "power_in"))
      (node (ref "U2") (pin "94") (pinfunction "VSS_94") (pintype "power_in"))
      (node (ref "U3") (pin "23") (pinfunction "VSS_23") (pintype "bidirectional"))
      (node (ref "U3") (pin "35") (pinfunction "VSS_35") (pintype "bidirectional"))
      (node (ref "U3") (pin "47") (pinfunction "VSS_47") (pintype "bidirectional"))
      (node (ref "U3") (pin "8") (pinfunction "VSSA_8") (pintype "bidirectional"))
      (node (ref "U4") (pin "P$10") (pinfunction "PGND_P$10") (pintype "bidirectional"))
      (node (ref "U4") (pin "P$15") (pinfunction "VSEL_P$15") (pintype "bidirectional"))
      (node (ref "U4") (pin "P$4") (pinfunction "GND_P$4") (pintype "bidirectional"))
      (node (ref "U4") (pin "P$6") (pinfunction "FB2_P$6") (pintype "bidirectional"))
      (node (ref "U5") (pin "3") (pinfunction "VSS_3") (pintype "bidirectional"))
      (node (ref "U5") (pin "EP") (pinfunction "PWPD_EP") (pintype "bidirectional"))
      (node (ref "U5") (pin "EP1") (pinfunction "PWPD_EP1") (pintype "bidirectional"))
      (node (ref "U5") (pin "EP2") (pinfunction "PWPD_EP2") (pintype "bidirectional"))
      (node (ref "U5") (pin "EP3") (pinfunction "PWPD_EP3") (pintype "bidirectional"))
      (node (ref "U5") (pin "EP4") (pinfunction "PWPD_EP4") (pintype "bidirectional"))
    )
    (net (code "29") (name "GPOUT") (class "Default")
      (node (ref "R7") (pin "1") (pinfunction "1_1") (pintype "passive"))
      (node (ref "U5") (pin "12") (pinfunction "GPOUT_12") (pintype "bidirectional"))
    )
    (net (code "30") (name "GSM_RST") (class "Default")
      (node (ref "U$1") (pin "P$2") (pinfunction "RST_P$2") (pintype "bidirectional"))
      (node (ref "U3") (pin "14") (pinfunction "PA4_14") (pintype "bidirectional"))
    )
    (net (code "31") (name "L0_LED1") (class "Default")
      (node (ref "R26") (pin "2") (pinfunction "2_2") (pintype "passive"))
      (node (ref "U3") (pin "20") (pinfunction "PB2_20") (pintype "bidirectional"))
    )
    (net (code "32") (name "L0_LED2") (class "Default")
      (node (ref "R31") (pin "2") (pinfunction "2_2") (pintype "passive"))
      (node (ref "U3") (pin "18") (pinfunction "PB0_18") (pintype "bidirectional"))
    )
    (net (code "33") (name "L0_RST") (class "Default")
      (node (ref "L0_PROGRAM") (pin "4") (pinfunction "4_4") (pintype "passive"))
      (node (ref "U3") (pin "7") (pinfunction "NRST_7") (pintype "bidirectional"))
    )
    (net (code "34") (name "L0_RX") (class "Default")
      (node (ref "MCU_UART") (pin "4") (pinfunction "4_4") (pintype "passive"))
      (node (ref "U3") (pin "43") (pinfunction "PB7_43") (pintype "bidirectional"))
    )
    (net (code "35") (name "L0_SWCLK") (class "Default")
      (node (ref "L0_PROGRAM") (pin "3") (pinfunction "3_3") (pintype "passive"))
      (node (ref "U3") (pin "37") (pinfunction "PA14_37") (pintype "bidirectional"))
    )
    (net (code "36") (name "L0_SWDIO") (class "Default")
      (node (ref "L0_PROGRAM") (pin "2") (pinfunction "2_2") (pintype "passive"))
      (node (ref "U3") (pin "34") (pinfunction "PA13_34") (pintype "bidirectional"))
    )
    (net (code "37") (name "L0_TX") (class "Default")
      (node (ref "MCU_UART") (pin "2") (pinfunction "2_2") (pintype "passive"))
      (node (ref "U3") (pin "42") (pinfunction "PB6_42") (pintype "bidirectional"))
    )
    (net (code "38") (name "LORA_EN") (class "Default")
      (node (ref "U$9") (pin "EN") (pinfunction "EN_EN") (pintype "bidirectional"))
      (node (ref "U3") (pin "30") (pinfunction "PA9_30") (pintype "bidirectional"))
    )
    (net (code "39") (name "LORA_INT") (class "Default")
      (node (ref "U$9") (pin "G0") (pinfunction "G0_G0") (pintype "bidirectional"))
      (node (ref "U3") (pin "29") (pinfunction "PA8_29") (pintype "bidirectional"))
    )
    (net (code "40") (name "LORA_RST") (class "Default")
      (node (ref "U$9") (pin "PRST") (pinfunction "RST_PRST") (pintype "bidirectional"))
      (node (ref "U3") (pin "31") (pinfunction "PA10_31") (pintype "bidirectional"))
    )
    (net (code "41") (name "MISO_LORA") (class "Default")
      (node (ref "U$9") (pin "MISO") (pinfunction "MISO_MISO") (pintype "bidirectional"))
      (node (ref "U3") (pin "27") (pinfunction "PB14_27") (pintype "bidirectional"))
    )
    (net (code "42") (name "MOSI_LORA") (class "Default")
      (node (ref "U$9") (pin "MOSI") (pinfunction "MOSI_MOSI") (pintype "bidirectional"))
      (node (ref "U3") (pin "28") (pinfunction "PB15_28") (pintype "bidirectional"))
    )
    (net (code "43") (name "Net-(3.3V-PadA)") (class "Default")
      (node (ref "3.3V") (pin "A") (pinfunction "A_A") (pintype "passive"))
      (node (ref "R30") (pin "1") (pinfunction "1_1") (pintype "passive"))
    )
    (net (code "44") (name "Net-(5V-PadA)") (class "Default")
      (node (ref "5V") (pin "A") (pinfunction "A_A") (pintype "passive"))
      (node (ref "R20") (pin "1") (pinfunction "1_1") (pintype "passive"))
    )
    (net (code "45") (name "Net-(BATT-2)") (class "Default")
      (node (ref "BATT") (pin "1") (pinfunction "2_1") (pintype "passive"))
      (node (ref "C21") (pin "1") (pinfunction "1_1") (pintype "passive"))
      (node (ref "R16") (pin "1") (pinfunction "1_1") (pintype "passive"))
      (node (ref "U5") (pin "6") (pinfunction "BAT_6") (pintype "bidirectional"))
      (node (ref "U5") (pin "8") (pinfunction "SRP_8") (pintype "bidirectional"))
    )
    (net (code "46") (name "Net-(CAMERA-Pad11)") (class "Default")
      (node (ref "CAMERA") (pin "11") (pinfunction "11_11") (pintype "passive"))
      (node (ref "R3") (pin "2") (pinfunction "2_2") (pintype "passive"))
    )
    (net (code "47") (name "Net-(CAMERA-Pad12)") (class "Default")
      (node (ref "CAMERA") (pin "12") (pinfunction "12_12") (pintype "passive"))
      (node (ref "R4") (pin "1") (pinfunction "1_1") (pintype "passive"))
    )
    (net (code "48") (name "Net-(CHRG-PadA)") (class "Default")
      (node (ref "CHRG") (pin "A") (pinfunction "A_A") (pintype "passive"))
      (node (ref "R10") (pin "1") (pinfunction "1_1") (pintype "passive"))
    )
    (net (code "49") (name "Net-(D1-PadA)") (class "Default")
      (node (ref "D1") (pin "A") (pinfunction "A_A") (pintype "passive"))
      (node (ref "SOLAR") (pin "PWR") (pinfunction "PWR_PWR") (pintype "power_in"))
    )
    (net (code "50") (name "Net-(DONE-PadA)") (class "Default")
      (node (ref "DONE") (pin "A") (pinfunction "A_A") (pintype "passive"))
      (node (ref "R11") (pin "1") (pinfunction "1_1") (pintype "passive"))
    )
    (net (code "51") (name "Net-(F7_LED1-PadA)") (class "Default")
      (node (ref "F7_LED1") (pin "A") (pinfunction "A_A") (pintype "passive"))
      (node (ref "R5") (pin "1") (pinfunction "1_1") (pintype "passive"))
    )
    (net (code "52") (name "Net-(F7_LED2-PadA)") (class "Default")
      (node (ref "F7_LED2") (pin "A") (pinfunction "A_A") (pintype "passive"))
      (node (ref "R6") (pin "1") (pinfunction "1_1") (pintype "passive"))
    )
    (net (code "53") (name "Net-(F7_LED3-PadA)") (class "Default")
      (node (ref "F7_LED3") (pin "A") (pinfunction "A_A") (pintype "passive"))
      (node (ref "R13") (pin "1") (pinfunction "1_1") (pintype "passive"))
    )
    (net (code "54") (name "Net-(IC1-PROG1)") (class "Default")
      (node (ref "IC1") (pin "P$13") (pinfunction "PROG1_P$13") (pintype "input"))
      (node (ref "R1") (pin "2") (pinfunction "2_2") (pintype "passive"))
    )
    (net (code "55") (name "Net-(IC1-PROG3)") (class "Default")
      (node (ref "IC1") (pin "P$12") (pinfunction "PROG3_P$12") (pintype "input"))
      (node (ref "R14") (pin "2") (pinfunction "2_2") (pintype "passive"))
    )
    (net (code "56") (name "Net-(IC1-STAT1{slash}LBO)") (class "Default")
      (node (ref "CHRG") (pin "C") (pinfunction "C_C") (pintype "passive"))
      (node (ref "IC1") (pin "P$8") (pinfunction "STAT1/LBO_P$8") (pintype "output"))
    )
    (net (code "57") (name "Net-(IC1-STAT2)") (class "Default")
      (node (ref "DONE") (pin "C") (pinfunction "C_C") (pintype "passive"))
      (node (ref "IC1") (pin "P$7") (pinfunction "STAT2_P$7") (pintype "output"))
    )
    (net (code "58") (name "Net-(IC1-THERM)") (class "Default")
      (node (ref "IC1") (pin "P$5") (pinfunction "THERM_P$5") (pintype "input"))
      (node (ref "R15") (pin "1") (pinfunction "1_1") (pintype "passive"))
    )
    (net (code "59") (name "Net-(IC1-VPCC)") (class "Default")
      (node (ref "IC1") (pin "P$2") (pinfunction "VPCC_P$2") (pintype "input"))
      (node (ref "R8") (pin "1") (pinfunction "1_1") (pintype "passive"))
      (node (ref "R9") (pin "1") (pinfunction "1_1") (pintype "passive"))
    )
    (net (code "60") (name "Net-(IC1-{slash}PG)") (class "Default")
      (node (ref "IC1") (pin "P$6") (pinfunction "/PG_P$6") (pintype "output"))
      (node (ref "PWR") (pin "C") (pinfunction "C_C") (pintype "passive"))
    )
    (net (code "61") (name "Net-(L0_LED1-PadA)") (class "Default")
      (node (ref "L0_LED1") (pin "A") (pinfunction "A_A") (pintype "passive"))
      (node (ref "R26") (pin "1") (pinfunction "1_1") (pintype "passive"))
    )
    (net (code "62") (name "Net-(L0_LED2-PadA)") (class "Default")
      (node (ref "L0_LED2") (pin "A") (pinfunction "A_A") (pintype "passive"))
      (node (ref "R31") (pin "1") (pinfunction "1_1") (pintype "passive"))
    )
    (net (code "63") (name "Net-(L1-1)") (class "Default")
      (node (ref "L1") (pin "P$1") (pinfunction "1_P$1") (pintype "passive"))
      (node (ref "U1") (pin "P$11") (pinfunction "L1_P$11") (pintype "bidirectional"))
    )
    (net (code "64") (name "Net-(L1-2)") (class "Default")
      (node (ref "L1") (pin "P$2") (pinfunction "2_P$2") (pintype "passive"))
      (node (ref "U1") (pin "P$9") (pinfunction "L2_P$9") (pintype "bidirectional"))
    )
    (net (code "65") (name "Net-(L2-1)") (class "Default")
      (node (ref "L2") (pin "P$1") (pinfunction "1_P$1") (pintype "passive"))
      (node (ref "U4") (pin "P$11") (pinfunction "L1_P$11") (pintype "bidirectional"))
    )
    (net (code "66") (name "Net-(L2-2)") (class "Default")
      (node (ref "L2") (pin "P$2") (pinfunction "2_P$2") (pintype "passive"))
      (node (ref "U4") (pin "P$9") (pinfunction "L2_P$9") (pintype "bidirectional"))
    )
    (net (code "67") (name "Net-(PWR-PadA)") (class "Default")
      (node (ref "PWR") (pin "A") (pinfunction "A_A") (pintype "passive"))
      (node (ref "R12") (pin "1") (pinfunction "1_1") (pintype "passive"))
    )
    (net (code "68") (name "Net-(Q1-D)") (class "Default")
      (node (ref "J3") (pin "2") (pinfunction "2_2") (pintype "passive"))
      (node (ref "Q1") (pin "3") (pinfunction "D_3") (pintype "bidirectional"))
      (node (ref "R23") (pin "1") (pinfunction "1_1") (pintype "passive"))
    )
    (net (code "69") (name "Net-(R15-Pad2)") (class "Default")
      (node (ref "R15") (pin "2") (pinfunction "2_2") (pintype "passive"))
      (node (ref "R2") (pin "2") (pinfunction "2_2") (pintype "passive"))
      (node (ref "RT2") (pin "2") (pinfunction "2_2") (pintype "passive"))
    )
    (net (code "70") (name "Net-(U$2-1)") (class "Default")
      (node (ref "C39") (pin "1") (pinfunction "1_1") (pintype "passive"))
      (node (ref "U$2") (pin "P$1") (pinfunction "1_P$1") (pintype "passive"))
      (node (ref "U2") (pin "23") (pinfunction "PH0-OSC_IN_23") (pintype "bidirectional"))
    )
    (net (code "71") (name "Net-(U$2-2)") (class "Default")
      (node (ref "C40") (pin "1") (pinfunction "1_1") (pintype "passive"))
      (node (ref "U$2") (pin "P$2") (pinfunction "2_P$2") (pintype "passive"))
      (node (ref "U2") (pin "24") (pinfunction "PH1-OSC_OUT_24") (pintype "bidirectional"))
    )
    (net (code "72") (name "Net-(U$3-1)") (class "Default")
      (node (ref "C41") (pin "1") (pinfunction "1_1") (pintype "passive"))
      (node (ref "U$3") (pin "P$1") (pinfunction "1_P$1") (pintype "passive"))
      (node (ref "U3") (pin "5") (pinfunction "PH0-OSC_IN_5") (pintype "bidirectional"))
    )
    (net (code "73") (name "Net-(U$3-2)") (class "Default")
      (node (ref "C42") (pin "1") (pinfunction "1_1") (pintype "passive"))
      (node (ref "U$3") (pin "P$2") (pinfunction "2_P$2") (pintype "passive"))
      (node (ref "U3") (pin "6") (pinfunction "PH1-OSC_OUT_6") (pintype "bidirectional"))
    )
    (net (code "74") (name "Net-(U1-FB)") (class "Default")
      (node (ref "R18") (pin "2") (pinfunction "2_2") (pintype "passive"))
      (node (ref "R19") (pin "1") (pinfunction "1_1") (pintype "passive"))
      (node (ref "U1") (pin "P$5") (pinfunction "FB_P$5") (pintype "bidirectional"))
    )
    (net (code "75") (name "Net-(U1-PS{slash}SYNC)") (class "Default")
      (node (ref "R17") (pin "1") (pinfunction "1_1") (pintype "passive"))
      (node (ref "U1") (pin "P$1") (pinfunction "PS/SYNC_P$1") (pintype "bidirectional"))
      (node (ref "U1") (pin "P$14") (pinfunction "~{EN}_P$14") (pintype "bidirectional"))
    )
    (net (code "76") (name "Net-(U1-VAUX)") (class "Default")
      (node (ref "C14") (pin "1") (pinfunction "1_1") (pintype "passive"))
      (node (ref "U1") (pin "P$3") (pinfunction "VAUX_P$3") (pintype "bidirectional"))
    )
    (net (code "77") (name "Net-(U2I-BOOT0(VPP))") (class "Default")
      (node (ref "R21") (pin "1") (pinfunction "1_1") (pintype "passive"))
      (node (ref "U2") (pin "138") (pinfunction "BOOT0(VPP)_138") (pintype "input"))
    )
    (net (code "78") (name "Net-(U3-BOOT0)") (class "Default")
      (node (ref "R24") (pin "2") (pinfunction "2_2") (pintype "passive"))
      (node (ref "U3") (pin "44") (pinfunction "BOOT0_44") (pintype "input"))
    )
    (net (code "79") (name "Net-(U4-FB)") (class "Default")
      (node (ref "R28") (pin "2") (pinfunction "2_2") (pintype "passive"))
      (node (ref "R29") (pin "1") (pinfunction "1_1") (pintype "passive"))
      (node (ref "U4") (pin "P$5") (pinfunction "FB_P$5") (pintype "bidirectional"))
    )
    (net (code "80") (name "Net-(U4-PS{slash}SYNC)") (class "Default")
      (node (ref "R27") (pin "1") (pinfunction "1_1") (pintype "passive"))
      (node (ref "U4") (pin "P$1") (pinfunction "PS/SYNC_P$1") (pintype "bidirectional"))
      (node (ref "U4") (pin "P$14") (pinfunction "~{EN}_P$14") (pintype "bidirectional"))
    )
    (net (code "81") (name "Net-(U4-VAUX)") (class "Default")
      (node (ref "C20") (pin "1") (pinfunction "1_1") (pintype "passive"))
      (node (ref "U4") (pin "P$3") (pinfunction "VAUX_P$3") (pintype "bidirectional"))
    )
    (net (code "82") (name "Net-(U5-BIN)") (class "Default")
      (node (ref "R25") (pin "2") (pinfunction "2_2") (pintype "passive"))
      (node (ref "U5") (pin "10") (pinfunction "BIN_10") (pintype "bidirectional"))
    )
    (net (code "83") (name "Net-(U5-VDD)") (class "Default")
      (node (ref "C22") (pin "1") (pinfunction "1_1") (pintype "passive"))
      (node (ref "U5") (pin "5") (pinfunction "VDD_5") (pintype "bidirectional"))
    )
    (net (code "84") (name "RX_GSM") (class "Default")
      (node (ref "U$1") (pin "P$14") (pinfunction "RX_P$14") (pintype "bidirectional"))
      (node (ref "U3") (pin "13") (pinfunction "PA3_13") (pintype "bidirectional"))
    )
    (net (code "85") (name "SCK_LORA") (class "Default")
      (node (ref "U$9") (pin "SCK") (pinfunction "SCK_SCK") (pintype "bidirectional"))
      (node (ref "U3") (pin "26") (pinfunction "PB13_26") (pintype "bidirectional"))
    )
    (net (code "86") (name "SERVO_PWM") (class "Default")
      (node (ref "Q1") (pin "2") (pinfunction "S_2") (pintype "bidirectional"))
      (node (ref "R22") (pin "1") (pinfunction "1_1") (pintype "passive"))
      (node (ref "U2") (pin "18") (pinfunction "PF6(TIM10_CH1,SPI5_NSS,SAI1_SD_B,UART7_RX,QUADSPI_BK1_IO3,ADC3_IN4)_18") (pintype "bidirectional"))
    )
    (net (code "87") (name "SYS_JTCK_SWCLK") (class "Default")
      (node (ref "J2") (pin "3") (pinfunction "3_3") (pintype "passive"))
      (node (ref "U2") (pin "109") (pinfunction "PA14(JTCK-SWCLK)_109") (pintype "bidirectional"))
    )
    (net (code "88") (name "SYS_JTMS_SWDIO") (class "Default")
      (node (ref "J2") (pin "2") (pinfunction "2_2") (pintype "passive"))
      (node (ref "U2") (pin "105") (pinfunction "PA13(JTMS-SWDIO)_105") (pintype "bidirectional"))
    )
    (net (code "89") (name "TX_GSM") (class "Default")
      (node (ref "U$1") (pin "P$13") (pinfunction "TX_P$13") (pintype "bidirectional"))
      (node (ref "U3") (pin "12") (pinfunction "PA2_12") (pintype "bidirectional"))
    )
    (net (code "90") (name "VBAT") (class "Default")
      (node (ref "C11") (pin "1") (pinfunction "1_1") (pintype "passive"))
      (node (ref "IC1") (pin "P$14") (pinfunction "VBAT1_P$14") (pintype "output"))
      (node (ref "IC1") (pin "P$15") (pinfunction "VBAT2_P$15") (pintype "output"))
      (node (ref "IC1") (pin "P$16") (pinfunction "VBAT3_P$16") (pintype "output"))
      (node (ref "R16") (pin "2") (pinfunction "2_2") (pintype "passive"))
      (node (ref "U5") (pin "7") (pinfunction "SRN_7") (pintype "bidirectional"))
    )
    (net (code "91") (name "VCAP1") (class "Default")
      (node (ref "C23") (pin "1") (pinfunction "1_1") (pintype "passive"))
      (node (ref "U2") (pin "71") (pinfunction "VCAP_1_71") (pintype "power_in"))
    )
    (net (code "92") (name "VCAP2") (class "Default")
      (node (ref "C24") (pin "1") (pinfunction "1_1") (pintype "passive"))
      (node (ref "U2") (pin "106") (pinfunction "VCAP_2_106") (pintype "power_in"))
    )
    (net (code "93") (name "VCC") (class "Default")
      (node (ref "C19") (pin "+") (pinfunction "+_+") (pintype "passive"))
      (node (ref "D1") (pin "C") (pinfunction "C_C") (pintype "passive"))
      (node (ref "IC1") (pin "P$17") (pinfunction "CE_P$17") (pintype "input"))
      (node (ref "IC1") (pin "P$18") (pinfunction "IN1_P$18") (pintype "input"))
      (node (ref "IC1") (pin "P$19") (pinfunction "IN2_P$19") (pintype "input"))
      (node (ref "IC1") (pin "P$3") (pinfunction "SEL_P$3") (pintype "input"))
      (node (ref "IC1") (pin "P$4") (pinfunction "PROG2_P$4") (pintype "input"))
      (node (ref "IC1") (pin "P$9") (pinfunction "/TE_P$9") (pintype "input"))
      (node (ref "R10") (pin "2") (pinfunction "2_2") (pintype "passive"))
      (node (ref "R11") (pin "2") (pinfunction "2_2") (pintype "passive"))
      (node (ref "R12") (pin "2") (pinfunction "2_2") (pintype "passive"))
      (node (ref "R8") (pin "2") (pinfunction "2_2") (pintype "passive"))
    )
    (net (code "94") (name "VOUT_CHARGER") (class "Default")
      (node (ref "C1") (pin "1") (pinfunction "1_1") (pintype "passive"))
      (node (ref "C10") (pin "1") (pinfunction "1_1") (pintype "passive"))
      (node (ref "C12") (pin "1") (pinfunction "1_1") (pintype "passive"))
      (node (ref "C13") (pin "1") (pinfunction "1_1") (pintype "passive"))
      (node (ref "C2") (pin "1") (pinfunction "1_1") (pintype "passive"))
      (node (ref "C50") (pin "1") (pinfunction "1_1") (pintype "passive"))
      (node (ref "C51") (pin "1") (pinfunction "1_1") (pintype "passive"))
      (node (ref "C7") (pin "1") (pinfunction "1_1") (pintype "passive"))
      (node (ref "C8") (pin "1") (pinfunction "1_1") (pintype "passive"))
      (node (ref "IC1") (pin "P$1") (pinfunction "OUT1_P$1") (pintype "output"))
      (node (ref "IC1") (pin "P$20") (pinfunction "OUT2_P$20") (pintype "output"))
      (node (ref "R17") (pin "2") (pinfunction "2_2") (pintype "passive"))
      (node (ref "R27") (pin "2") (pinfunction "2_2") (pintype "passive"))
      (node (ref "U1") (pin "P$12/13") (pinfunction "VIN_P$12/13") (pintype "bidirectional"))
      (node (ref "U4") (pin "P$12/13") (pinfunction "VIN_P$12/13") (pintype "bidirectional"))
    )
    (net (code "95") (name "unconnected-(U$1-AN-PadP$1)") (class "Default")
      (node (ref "U$1") (pin "P$1") (pinfunction "AN_P$1") (pintype "bidirectional"))
    )
    (net (code "96") (name "unconnected-(U$1-CS-PadP$3)") (class "Default")
      (node (ref "U$1") (pin "P$3") (pinfunction "CS_P$3") (pintype "bidirectional"))
    )
    (net (code "97") (name "unconnected-(U$1-INT-PadP$15)") (class "Default")
      (node (ref "U$1") (pin "P$15") (pinfunction "INT_P$15") (pintype "bidirectional"))
    )
    (net (code "98") (name "unconnected-(U$1-MISO-PadP$5)") (class "Default")
      (node (ref "U$1") (pin "P$5") (pinfunction "MISO_P$5") (pintype "bidirectional"))
    )
    (net (code "99") (name "unconnected-(U$1-MOSI-PadP$6)") (class "Default")
      (node (ref "U$1") (pin "P$6") (pinfunction "MOSI_P$6") (pintype "bidirectional"))
    )
    (net (code "100") (name "unconnected-(U$1-PWM-PadP$16)") (class "Default")
      (node (ref "U$1") (pin "P$16") (pinfunction "PWM_P$16") (pintype "bidirectional"))
    )
    (net (code "101") (name "unconnected-(U$1-SCK-PadP$4)") (class "Default")
      (node (ref "U$1") (pin "P$4") (pinfunction "SCK_P$4") (pintype "bidirectional"))
    )
    (net (code "102") (name "unconnected-(U$1-SCL-PadP$12)") (class "Default")
      (node (ref "U$1") (pin "P$12") (pinfunction "SCL_P$12") (pintype "bidirectional"))
    )
    (net (code "103") (name "unconnected-(U$1-SDA-PadP$11)") (class "Default")
      (node (ref "U$1") (pin "P$11") (pinfunction "SDA_P$11") (pintype "bidirectional"))
    )
    (net (code "104") (name "unconnected-(U$9-PadG1)") (class "Default")
      (node (ref "U$9") (pin "G1") (pinfunction "G1_G1") (pintype "bidirectional"))
    )
    (net (code "105") (name "unconnected-(U$9-PadG2)") (class "Default")
      (node (ref "U$9") (pin "G2") (pinfunction "G2_G2") (pintype "bidirectional"))
    )
    (net (code "106") (name "unconnected-(U$9-PadG3)") (class "Default")
      (node (ref "U$9") (pin "G3") (pinfunction "G3_G3") (pintype "bidirectional"))
    )
    (net (code "107") (name "unconnected-(U$9-PadG4)") (class "Default")
      (node (ref "U$9") (pin "G4") (pinfunction "G4_G4") (pintype "bidirectional"))
    )
    (net (code "108") (name "unconnected-(U$9-PadG5)") (class "Default")
      (node (ref "U$9") (pin "G5") (pinfunction "G5_G5") (pintype "bidirectional"))
    )
    (net (code "109") (name "unconnected-(U1-PG-PadP$2)") (class "Default")
      (node (ref "U1") (pin "P$2") (pinfunction "PG_P$2") (pintype "bidirectional"))
    )
    (net (code "110") (name "unconnected-(U2A-PA2(TIM2_CH3,TIM5_CH3,TIM9_CH1,USART2_TX,SAI2_SCK_B,ETH_MDIO,MDIOS_MDIO,LCD_R1,ADC1_IN2,ADC2_IN2,ADC3_IN2,WKUP2)-Pad36)") (class "Default")
      (node (ref "U2") (pin "36") (pinfunction "PA2(TIM2_CH3,TIM5_CH3,TIM9_CH1,USART2_TX,SAI2_SCK_B,ETH_MDIO,MDIOS_MDIO,LCD_R1,ADC1_IN2,ADC2_IN2,ADC3_IN2,WKUP2)_36") (pintype "bidirectional"))
    )
    (net (code "111") (name "unconnected-(U2A-PA3(TIM2_CH4,TIM5_CH4,TIM9_CH2,USART2_RX,LCD_B2,OTG_HS_ULPI_D0,ETH_MII_COL,LCD_B5,ADC1_IN3,ADC2_IN3,ADC3_IN3)-Pad37)") (class "Default")
      (node (ref "U2") (pin "37") (pinfunction "PA3(TIM2_CH4,TIM5_CH4,TIM9_CH2,USART2_RX,LCD_B2,OTG_HS_ULPI_D0,ETH_MII_COL,LCD_B5,ADC1_IN3,ADC2_IN3,ADC3_IN3)_37") (pintype "bidirectional"))
    )
    (net (code "112") (name "unconnected-(U2A-PA5(TIM2_CH1{slash}TIM2_ETR,TIM8_CH1N,SPI1_SCK{slash}I2S1_CK,SPI6_SCK,OTG_HS_ULPI_CK,LCD_R4,ADC1_IN5,ADC2_IN5,DAC_OUT2)-Pad41)") (class "Default")
      (node (ref "U2") (pin "41") (pinfunction "PA5(TIM2_CH1/TIM2_ETR,TIM8_CH1N,SPI1_SCK/I2S1_CK,SPI6_SCK,OTG_HS_ULPI_CK,LCD_R4,ADC1_IN5,ADC2_IN5,DAC_OUT2)_41") (pintype "bidirectional"))
    )
    (net (code "113") (name "unconnected-(U2A-PA7(TIM1_CH1N,TIM3_CH2,TIM8_CH1N,SPI1_MOSI{slash}I2S1_SD,SPI6_MOSI,TIM14_CH1,ETH_MII_RX_DV{slash}ETH_RMII_CRS_DV,FMC_SDNWE)-Pad43)") (class "Default")
      (node (ref "U2") (pin "43") (pinfunction "PA7(TIM1_CH1N,TIM3_CH2,TIM8_CH1N,SPI1_MOSI/I2S1_SD,SPI6_MOSI,TIM14_CH1,ETH_MII_RX_DV/ETH_RMII_CRS_DV,FMC_SDNWE)_43") (pintype "bidirectional"))
    )
    (net (code "114") (name "unconnected-(U2A-PA9(TIM1_CH2,I2C3_SMBA,SPI2_SCK{slash}I2S2_CK,USART1_TX,DCMI_D0,LCD_R5)-Pad101)") (class "Default")
      (node (ref "U2") (pin "101") (pinfunction "PA9(TIM1_CH2,I2C3_SMBA,SPI2_SCK/I2S2_CK,USART1_TX,DCMI_D0,LCD_R5)_101") (pintype "bidirectional"))
    )
    (net (code "115") (name "unconnected-(U2A-PA10(TIM1_CH3,USART1_RX,LCD_B4,OTG_FS_ID,MDIOS_MDIO,DCMI_D1,LCD_B1)-Pad102)") (class "Default")
      (node (ref "U2") (pin "102") (pinfunction "PA10(TIM1_CH3,USART1_RX,LCD_B4,OTG_FS_ID,MDIOS_MDIO,DCMI_D1,LCD_B1)_102") (pintype "bidirectional"))
    )
    (net (code "116") (name "unconnected-(U2A-PA11(TIM1_CH4,SPI2_NSS{slash}I2S2_WS,UART4_RX,USART1_CTS,CAN1_RX,OTG_FS_DM,LCD_R4)-Pad103)") (class "Default")
      (node (ref "U2") (pin "103") (pinfunction "PA11(TIM1_CH4,SPI2_NSS/I2S2_WS,UART4_RX,USART1_CTS,CAN1_RX,OTG_FS_DM,LCD_R4)_103") (pintype "bidirectional"))
    )
    (net (code "117") (name "unconnected-(U2A-PA12(TIM1_ETR,SPI2_SCK{slash}I2S2_CK,UART4_TX,USART1_RTS,CAN1_TX,OTG_FS_DP,LCD_R5)-Pad104)") (class "Default")
      (node (ref "U2") (pin "104") (pinfunction "PA12(TIM1_ETR,SPI2_SCK/I2S2_CK,UART4_TX,USART1_RTS,CAN1_TX,OTG_FS_DP,LCD_R5)_104") (pintype "bidirectional"))
    )
    (net (code "118") (name "unconnected-(U2A-PA15(JTDI,TIM2_CH1{slash}TIM2_ETR,HDMI_CEC,SPI_NSS{slash}I2S1_WS,SPI3_NSS{slash}I2S3_WS,SPI6_NSS,UART4_RTS,CAN3_TX,UART7_TX)-Pad110)") (class "Default")
      (node (ref "U2") (pin "110") (pinfunction "PA15(JTDI,TIM2_CH1/TIM2_ETR,HDMI_CEC,SPI_NSS/I2S1_WS,SPI3_NSS/I2S3_WS,SPI6_NSS,UART4_RTS,CAN3_TX,UART7_TX)_110") (pintype "bidirectional"))
    )
    (net (code "119") (name "unconnected-(U2B-PB0(TIM1_CH2N,TIM3_CH3,TIM8_CH2N,DFSDM1_CKOUT,UART4_CTS,LCD_R3,OTG_HS_ULPI_D1,ETH_MII_RXD2,LCD_G1,ADC1_IN8,ADC2_IN8)-Pad46)") (class "Default")
      (node (ref "U2") (pin "46") (pinfunction "PB0(TIM1_CH2N,TIM3_CH3,TIM8_CH2N,DFSDM1_CKOUT,UART4_CTS,LCD_R3,OTG_HS_ULPI_D1,ETH_MII_RXD2,LCD_G1,ADC1_IN8,ADC2_IN8)_46") (pintype "bidirectional"))
    )
    (net (code "120") (name "unconnected-(U2B-PB1(TIM1_CH3N,TIM3_CH4,TIM8_CH3N,DFSDM1_DATIN1,LCD_R6,OTG_HS_ULPI_D2,ETH_MII_RXD3,LCD_G0,ADC1_IN9,ADC2_IN9)-Pad47)") (class "Default")
      (node (ref "U2") (pin "47") (pinfunction "PB1(TIM1_CH3N,TIM3_CH4,TIM8_CH3N,DFSDM1_DATIN1,LCD_R6,OTG_HS_ULPI_D2,ETH_MII_RXD3,LCD_G0,ADC1_IN9,ADC2_IN9)_47") (pintype "bidirectional"))
    )
    (net (code "121") (name "unconnected-(U2B-PB2(SAI1_SD_A,SPI3_MOSI{slash}I2S3_SD,QUADSPI_CLK,DFSDM1_CKIN1)-Pad48)") (class "Default")
      (node (ref "U2") (pin "48") (pinfunction "PB2(SAI1_SD_A,SPI3_MOSI/I2S3_SD,QUADSPI_CLK,DFSDM1_CKIN1)_48") (pintype "bidirectional"))
    )
    (net (code "122") (name "unconnected-(U2B-PB3(JTDO{slash}TRACESWO,TIM2_CH2,SPI1_SCK{slash}I2S1_CK,SPI3_SCK{slash}I2S3_CK,SPI6_SCK,SDMMC2_D2,CAN3_RX,UART7_RX)-Pad133)") (class "Default")
      (node (ref "U2") (pin "133") (pinfunction "PB3(JTDO/TRACESWO,TIM2_CH2,SPI1_SCK/I2S1_CK,SPI3_SCK/I2S3_CK,SPI6_SCK,SDMMC2_D2,CAN3_RX,UART7_RX)_133") (pintype "bidirectional"))
    )
    (net (code "123") (name "unconnected-(U2B-PB4(NJTRST,TIM3_CH1,SPI1_MISO,SPI3_MISO,SPI2_NSS{slash}I2S2_WS,SPI6_MISO,SDMMC2_D3,CAN3_TX,UART7_TX)-Pad134)") (class "Default")
      (node (ref "U2") (pin "134") (pinfunction "PB4(NJTRST,TIM3_CH1,SPI1_MISO,SPI3_MISO,SPI2_NSS/I2S2_WS,SPI6_MISO,SDMMC2_D3,CAN3_TX,UART7_TX)_134") (pintype "bidirectional"))
    )
    (net (code "124") (name "unconnected-(U2B-PB5(UART5_RX,TIM3_CH2,I2C1_SMBA,SPI1_MOSI{slash}I2S1_SD,SPI3_MOSI{slash}I2S3_SD,SPI6_MOSI,CAN2_RX,OTG_HS_ULPI_D7,ETH_PPS_OUT,FMC_SDCKE1,DCMI_D10,LCD_G7)-Pad135)") (class "Default")
      (node (ref "U2") (pin "135") (pinfunction "PB5(UART5_RX,TIM3_CH2,I2C1_SMBA,SPI1_MOSI/I2S1_SD,SPI3_MOSI/I2S3_SD,SPI6_MOSI,CAN2_RX,OTG_HS_ULPI_D7,ETH_PPS_OUT,FMC_SDCKE1,DCMI_D10,LCD_G7)_135") (pintype "bidirectional"))
    )
    (net (code "125") (name "unconnected-(U2B-PB6(UART5_TX,TIM4_CH1,HDMI_CEC,I2C1_SCL,DFSDM1_DATIN5,USART1_TX,CAN2_TX,QUADSPI_BK1_NCS,I2C4_SCL,FMC_SDNE1,DCMI_D5)-Pad136)") (class "Default")
      (node (ref "U2") (pin "136") (pinfunction "PB6(UART5_TX,TIM4_CH1,HDMI_CEC,I2C1_SCL,DFSDM1_DATIN5,USART1_TX,CAN2_TX,QUADSPI_BK1_NCS,I2C4_SCL,FMC_SDNE1,DCMI_D5)_136") (pintype "bidirectional"))
    )
    (net (code "126") (name "unconnected-(U2B-PB7(TIM4_CH2,I2C1_SDA,DFSDM1_CKIN5,USART1_RX,I2C4_SDA,FMC_NL,DCMI_VSYNC)-Pad137)") (class "Default")
      (node (ref "U2") (pin "137") (pinfunction "PB7(TIM4_CH2,I2C1_SDA,DFSDM1_CKIN5,USART1_RX,I2C4_SDA,FMC_NL,DCMI_VSYNC)_137") (pintype "bidirectional"))
    )
    (net (code "127") (name "unconnected-(U2B-PB10(TIM2_CH3,I2C2_SCL,SPI_SCK{slash}I2S2_CK,DFSDM1_DATIN7,USART3_TX,QUADSPI_BK1_NCS,OTG_HS_ULPI_D3,ETH_MII_RX_ER,LCD_G4)-Pad69)") (class "Default")
      (node (ref "U2") (pin "69") (pinfunction "PB10(TIM2_CH3,I2C2_SCL,SPI_SCK/I2S2_CK,DFSDM1_DATIN7,USART3_TX,QUADSPI_BK1_NCS,OTG_HS_ULPI_D3,ETH_MII_RX_ER,LCD_G4)_69") (pintype "bidirectional"))
    )
    (net (code "128") (name "unconnected-(U2B-PB11(TIM2_CH4,I2C2_SDA,DFSDM1_CKIN7,USART3_RX,OTG_HS_ULPI_D4,ETH_MII_TX_EN{slash}ETH_RMII_TX,DSI_TE,LCD_G5)-Pad70)") (class "Default")
      (node (ref "U2") (pin "70") (pinfunction "PB11(TIM2_CH4,I2C2_SDA,DFSDM1_CKIN7,USART3_RX,OTG_HS_ULPI_D4,ETH_MII_TX_EN/ETH_RMII_TX,DSI_TE,LCD_G5)_70") (pintype "bidirectional"))
    )
    (net (code "129") (name "unconnected-(U2B-PB12(TIM1_BKIN,I2C2_SMBA,SPI2_NSS{slash}I2S2_WS,DFSDM1_DATIN1,USART3_CK,UART5_RX,CAN2_RX,OTG_HS_ULPI_D5,ETH_MII_TXD0{slash}ETH_RMII_TXD0,OTG_HS_ID)-Pad73)") (class "Default")
      (node (ref "U2") (pin "73") (pinfunction "PB12(TIM1_BKIN,I2C2_SMBA,SPI2_NSS/I2S2_WS,DFSDM1_DATIN1,USART3_CK,UART5_RX,CAN2_RX,OTG_HS_ULPI_D5,ETH_MII_TXD0/ETH_RMII_TXD0,OTG_HS_ID)_73") (pintype "bidirectional"))
    )
    (net (code "130") (name "unconnected-(U2B-PB13(TIM1_CH1N,SPI2_SCK{slash}I2S2_CK,DFSDM1_CKIN1,USART3_CTS,UART5_TX,CAN2_TX,OTG_HS_ULPI_D6,ETH_MII_TXD1{slash}ETH_RMII_TXD1)-Pad74)") (class "Default")
      (node (ref "U2") (pin "74") (pinfunction "PB13(TIM1_CH1N,SPI2_SCK/I2S2_CK,DFSDM1_CKIN1,USART3_CTS,UART5_TX,CAN2_TX,OTG_HS_ULPI_D6,ETH_MII_TXD1/ETH_RMII_TXD1)_74") (pintype "bidirectional"))
    )
    (net (code "131") (name "unconnected-(U2B-PB14(TIM1_CH2N,TIM8_CH2N,USART1_TX,SPI2_MISO,DFSDM1_DATIN2,USART3_RTS,UART4_RTS,TIM12_CH1,SDMMC2_D0,OTG_HS_DM)-Pad75)") (class "Default")
      (node (ref "U2") (pin "75") (pinfunction "PB14(TIM1_CH2N,TIM8_CH2N,USART1_TX,SPI2_MISO,DFSDM1_DATIN2,USART3_RTS,UART4_RTS,TIM12_CH1,SDMMC2_D0,OTG_HS_DM)_75") (pintype "bidirectional"))
    )
    (net (code "132") (name "unconnected-(U2B-PB15(RTC_REFIN,TIM1_CH3N,TIM8_CH3N,USART1_RX,SPI2_MOSI{slash}I2S2_SD,DFSDM1_CKIN2,UART4_CTS,TIM12_CH2,SDMMC2_D1,OTG_HS_DP)-Pad76)") (class "Default")
      (node (ref "U2") (pin "76") (pinfunction "PB15(RTC_REFIN,TIM1_CH3N,TIM8_CH3N,USART1_RX,SPI2_MOSI/I2S2_SD,DFSDM1_CKIN2,UART4_CTS,TIM12_CH2,SDMMC2_D1,OTG_HS_DP)_76") (pintype "bidirectional"))
    )
    (net (code "133") (name "unconnected-(U2C-PC0(DFSDM1_CKIN0,DFSDM1_DATIN4,SAI2_FS_B,OTG_HS_ULPI_STP,FMC_SDNWE,LCD_R5,ADC1_IN10,ADC2_IN10,ADC3_IN10)-Pad26)") (class "Default")
      (node (ref "U2") (pin "26") (pinfunction "PC0(DFSDM1_CKIN0,DFSDM1_DATIN4,SAI2_FS_B,OTG_HS_ULPI_STP,FMC_SDNWE,LCD_R5,ADC1_IN10,ADC2_IN10,ADC3_IN10)_26") (pintype "bidirectional"))
    )
    (net (code "134") (name "unconnected-(U2C-PC1(TRACED0,DFSDM1_DATIN0,SAI2_MOSI{slash}I2S2_SD,SAI1_SD_A,DFSDM1_CKIN4,ETH_MDC,MDIOS_MDC,ADC1_IN11,ADC2_IN11,ADC3_IN11,RTC_TAMP3)-Pad27)") (class "Default")
      (node (ref "U2") (pin "27") (pinfunction "PC1(TRACED0,DFSDM1_DATIN0,SAI2_MOSI/I2S2_SD,SAI1_SD_A,DFSDM1_CKIN4,ETH_MDC,MDIOS_MDC,ADC1_IN11,ADC2_IN11,ADC3_IN11,RTC_TAMP3)_27") (pintype "bidirectional"))
    )
    (net (code "135") (name "unconnected-(U2C-PC2(DFSDM1_CKIN1,SPI2_MISO,DFSDM1_CKOUT,OTG_HS_ULPI_DIR,ETH_MII_TXD2,FMC_SDNE0,ADC1_IN12,ADC2_IN12,ADC3_IN13)-Pad28)") (class "Default")
      (node (ref "U2") (pin "28") (pinfunction "PC2(DFSDM1_CKIN1,SPI2_MISO,DFSDM1_CKOUT,OTG_HS_ULPI_DIR,ETH_MII_TXD2,FMC_SDNE0,ADC1_IN12,ADC2_IN12,ADC3_IN13)_28") (pintype "bidirectional"))
    )
    (net (code "136") (name "unconnected-(U2C-PC3(DFSDM1_DATIN1,SPI2_MOSI{slash}I2S2_SD,OTG_HS_ULPI_NXT,ETH_MII_TX_CLK,FMC_SDCKE0,ADC1_IN13,ADC2_IN13,ADC3_IN13)-Pad29)") (class "Default")
      (node (ref "U2") (pin "29") (pinfunction "PC3(DFSDM1_DATIN1,SPI2_MOSI/I2S2_SD,OTG_HS_ULPI_NXT,ETH_MII_TX_CLK,FMC_SDCKE0,ADC1_IN13,ADC2_IN13,ADC3_IN13)_29") (pintype "bidirectional"))
    )
    (net (code "137") (name "unconnected-(U2C-PC4(DFSDM1_CKIN2,I2S1_MCK,SPDIF_RX2,ETH_MII_RXD0{slash}ETH_RMII_RXD0,FMC_SDNE0,ADC1_IN14,ADC2_IN14)-Pad44)") (class "Default")
      (node (ref "U2") (pin "44") (pinfunction "PC4(DFSDM1_CKIN2,I2S1_MCK,SPDIF_RX2,ETH_MII_RXD0/ETH_RMII_RXD0,FMC_SDNE0,ADC1_IN14,ADC2_IN14)_44") (pintype "bidirectional"))
    )
    (net (code "138") (name "unconnected-(U2C-PC5(DFSDM1_DATIN2,SPDIF_RX3,ETH_MII_RXD1{slash}ETH_RMII_RXD1,FMC_SDCKE0,ADC1_IN15,ADC2_IN15)-Pad45)") (class "Default")
      (node (ref "U2") (pin "45") (pinfunction "PC5(DFSDM1_DATIN2,SPDIF_RX3,ETH_MII_RXD1/ETH_RMII_RXD1,FMC_SDCKE0,ADC1_IN15,ADC2_IN15)_45") (pintype "bidirectional"))
    )
    (net (code "139") (name "unconnected-(U2C-PC10(DFSDM1_CKIN5,SPI3_SCK{slash}I2S3_CK,USART3_TX,UART4_TX,QUADSPI_BK1_IO1,SDMMC1_D2,DCMI_D8,LCD_R2)-Pad111)") (class "Default")
      (node (ref "U2") (pin "111") (pinfunction "PC10(DFSDM1_CKIN5,SPI3_SCK/I2S3_CK,USART3_TX,UART4_TX,QUADSPI_BK1_IO1,SDMMC1_D2,DCMI_D8,LCD_R2)_111") (pintype "bidirectional"))
    )
    (net (code "140") (name "unconnected-(U2C-PC12(TRACED3,SPI3_MOSI{slash}I2S3_SD,USART3_CK,UART5_TX,SDMMC1_CK,DCMI_D9)-Pad113)") (class "Default")
      (node (ref "U2") (pin "113") (pinfunction "PC12(TRACED3,SPI3_MOSI/I2S3_SD,USART3_CK,UART5_TX,SDMMC1_CK,DCMI_D9)_113") (pintype "bidirectional"))
    )
    (net (code "141") (name "unconnected-(U2C-PC13(RTC_TAMP2{slash}RTS_TS{slash}WKUP5)-Pad7)") (class "Default")
      (node (ref "U2") (pin "7") (pinfunction "PC13(RTC_TAMP2/RTS_TS/WKUP5)_7") (pintype "bidirectional"))
    )
    (net (code "142") (name "unconnected-(U2C-PC14-OSC32_IN-Pad8)") (class "Default")
      (node (ref "U2") (pin "8") (pinfunction "PC14-OSC32_IN_8") (pintype "bidirectional"))
    )
    (net (code "143") (name "unconnected-(U2C-PC15-OSC32_OUT-Pad9)") (class "Default")
      (node (ref "U2") (pin "9") (pinfunction "PC15-OSC32_OUT_9") (pintype "bidirectional"))
    )
    (net (code "144") (name "unconnected-(U2D-PD0(DFSDN1_CKIN6,DFSDM1_DATIN7,UART4_RX,CAN1_RX,FMC_D2)-Pad114)") (class "Default")
      (node (ref "U2") (pin "114") (pinfunction "PD0(DFSDN1_CKIN6,DFSDM1_DATIN7,UART4_RX,CAN1_RX,FMC_D2)_114") (pintype "bidirectional"))
    )
    (net (code "145") (name "unconnected-(U2D-PD1(DFSDN1_DATIN6,DFSDM1_CKIN7,UART4_TX,CAN1_TX,FMC_D3)-Pad115)") (class "Default")
      (node (ref "U2") (pin "115") (pinfunction "PD1(DFSDN1_DATIN6,DFSDM1_CKIN7,UART4_TX,CAN1_TX,FMC_D3)_115") (pintype "bidirectional"))
    )
    (net (code "146") (name "unconnected-(U2D-PD2(TRACED2,TIM3_ETR,UART5_RX,SDMMC1_CMD,DCMI_D11)-Pad116)") (class "Default")
      (node (ref "U2") (pin "116") (pinfunction "PD2(TRACED2,TIM3_ETR,UART5_RX,SDMMC1_CMD,DCMI_D11)_116") (pintype "bidirectional"))
    )
    (net (code "147") (name "unconnected-(U2D-PD4(DFSDM1_CKIN0,USART2_RTS,FMC_NOE)-Pad118)") (class "Default")
      (node (ref "U2") (pin "118") (pinfunction "PD4(DFSDM1_CKIN0,USART2_RTS,FMC_NOE)_118") (pintype "bidirectional"))
    )
    (net (code "148") (name "unconnected-(U2D-PD5(USART2_TX,FMC_NWE)-Pad119)") (class "Default")
      (node (ref "U2") (pin "119") (pinfunction "PD5(USART2_TX,FMC_NWE)_119") (pintype "bidirectional"))
    )
    (net (code "149") (name "unconnected-(U2D-PD6(DFSDM1_CKIN4,SPI4_MOSI{slash}I2S3_SD,SAI1_SD_A,USART2_RX,DFSDM1_DATIN1,SDMMC2_CK,FMC_NWAIT,DCMI_D10,LCD_B2)-Pad122)") (class "Default")
      (node (ref "U2") (pin "122") (pinfunction "PD6(DFSDM1_CKIN4,SPI4_MOSI/I2S3_SD,SAI1_SD_A,USART2_RX,DFSDM1_DATIN1,SDMMC2_CK,FMC_NWAIT,DCMI_D10,LCD_B2)_122") (pintype "bidirectional"))
    )
    (net (code "150") (name "unconnected-(U2D-PD7(DFSDM1_DATIN4,SPI4_MOSI{slash}I2S1_SD,DFSDM1_CKIN1,USART2_CK,SPDIF_RX0,SDMMC2_CMD,FMC_NE1)-Pad123)") (class "Default")
      (node (ref "U2") (pin "123") (pinfunction "PD7(DFSDM1_DATIN4,SPI4_MOSI/I2S1_SD,DFSDM1_CKIN1,USART2_CK,SPDIF_RX0,SDMMC2_CMD,FMC_NE1)_123") (pintype "bidirectional"))
    )
    (net (code "151") (name "unconnected-(U2D-PD8(DFSDM1_CKIN3,USART3_TX,SPDIF_RX1,FMC_D13)-Pad77)") (class "Default")
      (node (ref "U2") (pin "77") (pinfunction "PD8(DFSDM1_CKIN3,USART3_TX,SPDIF_RX1,FMC_D13)_77") (pintype "bidirectional"))
    )
    (net (code "152") (name "unconnected-(U2D-PD9(DFSDM1_DATIN3,USART3_RX,FMC_D14)-Pad78)") (class "Default")
      (node (ref "U2") (pin "78") (pinfunction "PD9(DFSDM1_DATIN3,USART3_RX,FMC_D14)_78") (pintype "bidirectional"))
    )
    (net (code "153") (name "unconnected-(U2D-PD10(DFSDM1_CKOUT,USART3_CK,FMC_D15,LCD_B3)-Pad79)") (class "Default")
      (node (ref "U2") (pin "79") (pinfunction "PD10(DFSDM1_CKOUT,USART3_CK,FMC_D15,LCD_B3)_79") (pintype "bidirectional"))
    )
    (net (code "154") (name "unconnected-(U2D-PD11(I2C4_SMBA,USART3_CTS,QUADSPI_BK1_IO0,SAI2_SD_A,FMC_A16{slash}FMC_CLE)-Pad80)") (class "Default")
      (node (ref "U2") (pin "80") (pinfunction "PD11(I2C4_SMBA,USART3_CTS,QUADSPI_BK1_IO0,SAI2_SD_A,FMC_A16/FMC_CLE)_80") (pintype "bidirectional"))
    )
    (net (code "155") (name "unconnected-(U2D-PD14(TIM4_CH3,UART8_CTS,FMC_D0)-Pad85)") (class "Default")
      (node (ref "U2") (pin "85") (pinfunction "PD14(TIM4_CH3,UART8_CTS,FMC_D0)_85") (pintype "bidirectional"))
    )
    (net (code "156") (name "unconnected-(U2D-PD15(TIM4_CH4,UART8_RTS,FMC_D1)-Pad86)") (class "Default")
      (node (ref "U2") (pin "86") (pinfunction "PD15(TIM4_CH4,UART8_RTS,FMC_D1)_86") (pintype "bidirectional"))
    )
    (net (code "157") (name "unconnected-(U2E-PE2(TRACECLK,SP14_SCK,SAI1_MCLK_A,QUADSPI_BK1_IO2,ETH_MII_TXD3,FMC_A23)-Pad1)") (class "Default")
      (node (ref "U2") (pin "1") (pinfunction "PE2(TRACECLK,SP14_SCK,SAI1_MCLK_A,QUADSPI_BK1_IO2,ETH_MII_TXD3,FMC_A23)_1") (pintype "bidirectional"))
    )
    (net (code "158") (name "unconnected-(U2E-PE3(TRACED0,SAI1_SD_B,FMC_A19)-Pad2)") (class "Default")
      (node (ref "U2") (pin "2") (pinfunction "PE3(TRACED0,SAI1_SD_B,FMC_A19)_2") (pintype "bidirectional"))
    )
    (net (code "159") (name "unconnected-(U2E-PE4(TRACED1,SPI4_NSS,SAI1_FS_A,DFSDM1_DATIN3,FMC_A20,DCMI_D4,LCD_B0)-Pad3)") (class "Default")
      (node (ref "U2") (pin "3") (pinfunction "PE4(TRACED1,SPI4_NSS,SAI1_FS_A,DFSDM1_DATIN3,FMC_A20,DCMI_D4,LCD_B0)_3") (pintype "bidirectional"))
    )
    (net (code "160") (name "unconnected-(U2E-PE5(TRACED2,TIM9_CH1,SPI4_MISO,SAI1_SCK_A,DFSDM1_CKIN3,FMC_A21,DCMI_D6,LCD_G0)-Pad4)") (class "Default")
      (node (ref "U2") (pin "4") (pinfunction "PE5(TRACED2,TIM9_CH1,SPI4_MISO,SAI1_SCK_A,DFSDM1_CKIN3,FMC_A21,DCMI_D6,LCD_G0)_4") (pintype "bidirectional"))
    )
    (net (code "161") (name "unconnected-(U2E-PE6(TRACED3,TIM1_BKIN2,TIM9_CH2,SPI4_MOSI,SAI1_SD_A,SAI2_MCLK_B,FMC_A22,DCMI_D7,LCD_G1)-Pad5)") (class "Default")
      (node (ref "U2") (pin "5") (pinfunction "PE6(TRACED3,TIM1_BKIN2,TIM9_CH2,SPI4_MOSI,SAI1_SD_A,SAI2_MCLK_B,FMC_A22,DCMI_D7,LCD_G1)_5") (pintype "bidirectional"))
    )
    (net (code "162") (name "unconnected-(U2E-PE8(TIM1_CH1N,DFSDM1_CKIN2,UART7_TX,QUADSPI_BK2_IO1,FMC_D5)-Pad59)") (class "Default")
      (node (ref "U2") (pin "59") (pinfunction "PE8(TIM1_CH1N,DFSDM1_CKIN2,UART7_TX,QUADSPI_BK2_IO1,FMC_D5)_59") (pintype "bidirectional"))
    )
    (net (code "163") (name "unconnected-(U2E-PE9(TIM1_CH1,DFSDM1_CKOUT,UART7_RTS,QUADSPI_BK2_IO2,FMC_D6)-Pad60)") (class "Default")
      (node (ref "U2") (pin "60") (pinfunction "PE9(TIM1_CH1,DFSDM1_CKOUT,UART7_RTS,QUADSPI_BK2_IO2,FMC_D6)_60") (pintype "bidirectional"))
    )
    (net (code "164") (name "unconnected-(U2E-PE10(TIM1_CH2N,DFSDM1_DATIN4,UART7_CTS,QUADSPI_BK2_IO3,FMC_D7)-Pad63)") (class "Default")
      (node (ref "U2") (pin "63") (pinfunction "PE10(TIM1_CH2N,DFSDM1_DATIN4,UART7_CTS,QUADSPI_BK2_IO3,FMC_D7)_63") (pintype "bidirectional"))
    )
    (net (code "165") (name "unconnected-(U2E-PE11(TIM1_CH2,SPI4_NSS,DFSDM1_CKIN4,SAI2_SD_B,FMC_D8,LCD_G3)-Pad64)") (class "Default")
      (node (ref "U2") (pin "64") (pinfunction "PE11(TIM1_CH2,SPI4_NSS,DFSDM1_CKIN4,SAI2_SD_B,FMC_D8,LCD_G3)_64") (pintype "bidirectional"))
    )
    (net (code "166") (name "unconnected-(U2E-PE12(TIM1_CH3N,SPI4_SCK,DFSDM1_DATIN5,SAI2_SCK_B,FMC_D9,LCD_B4)-Pad65)") (class "Default")
      (node (ref "U2") (pin "65") (pinfunction "PE12(TIM1_CH3N,SPI4_SCK,DFSDM1_DATIN5,SAI2_SCK_B,FMC_D9,LCD_B4)_65") (pintype "bidirectional"))
    )
    (net (code "167") (name "unconnected-(U2E-PE13(TIM1_CH3,SPI4_MISO,DFSDM1_CKIN5,SAI2_FS_B,FMC_D10,LCD_DE)-Pad66)") (class "Default")
      (node (ref "U2") (pin "66") (pinfunction "PE13(TIM1_CH3,SPI4_MISO,DFSDM1_CKIN5,SAI2_FS_B,FMC_D10,LCD_DE)_66") (pintype "bidirectional"))
    )
    (net (code "168") (name "unconnected-(U2E-PE14(TIM1_CH4,SPI4_MOSI,SAI2_MCLK_B,FMC_D11,LCD_CLK)-Pad67)") (class "Default")
      (node (ref "U2") (pin "67") (pinfunction "PE14(TIM1_CH4,SPI4_MOSI,SAI2_MCLK_B,FMC_D11,LCD_CLK)_67") (pintype "bidirectional"))
    )
    (net (code "169") (name "unconnected-(U2E-PE15(TIM1_BKIN,FMC_D12,LCD_R7)-Pad68)") (class "Default")
      (node (ref "U2") (pin "68") (pinfunction "PE15(TIM1_BKIN,FMC_D12,LCD_R7)_68") (pintype "bidirectional"))
    )
    (net (code "170") (name "unconnected-(U2F-PF0(I2C2_SDA,FMC_A0)-Pad10)") (class "Default")
      (node (ref "U2") (pin "10") (pinfunction "PF0(I2C2_SDA,FMC_A0)_10") (pintype "bidirectional"))
    )
    (net (code "171") (name "unconnected-(U2F-PF1(I2C2_SCL,FMC_A1)-Pad11)") (class "Default")
      (node (ref "U2") (pin "11") (pinfunction "PF1(I2C2_SCL,FMC_A1)_11") (pintype "bidirectional"))
    )
    (net (code "172") (name "unconnected-(U2F-PF2(I2C2_SMBA,FCM_A2)-Pad12)") (class "Default")
      (node (ref "U2") (pin "12") (pinfunction "PF2(I2C2_SMBA,FCM_A2)_12") (pintype "bidirectional"))
    )
    (net (code "173") (name "unconnected-(U2F-PF3(FMC_A3,ADC3_IN9)-Pad13)") (class "Default")
      (node (ref "U2") (pin "13") (pinfunction "PF3(FMC_A3,ADC3_IN9)_13") (pintype "bidirectional"))
    )
    (net (code "174") (name "unconnected-(U2F-PF4(FMC_A4,ADC3_IN14)-Pad14)") (class "Default")
      (node (ref "U2") (pin "14") (pinfunction "PF4(FMC_A4,ADC3_IN14)_14") (pintype "bidirectional"))
    )
    (net (code "175") (name "unconnected-(U2F-PF5(FMC_A5,ADC3_IN15)-Pad15)") (class "Default")
      (node (ref "U2") (pin "15") (pinfunction "PF5(FMC_A5,ADC3_IN15)_15") (pintype "bidirectional"))
    )
    (net (code "176") (name "unconnected-(U2F-PF7(TIM11_CH1,SPI5_SCK,SAI1_MCK_B,UART7_TX,QUADSPI_BK1_IO2,ADC3_IN5)-Pad19)") (class "Default")
      (node (ref "U2") (pin "19") (pinfunction "PF7(TIM11_CH1,SPI5_SCK,SAI1_MCK_B,UART7_TX,QUADSPI_BK1_IO2,ADC3_IN5)_19") (pintype "bidirectional"))
    )
    (net (code "177") (name "unconnected-(U2F-PF8(SPI5_MISO,SAI1_SCK_B,UART7_RTS,TIM13_CH1,QUADSPI_BK1_IO0,ADC3_IN6)-Pad20)") (class "Default")
      (node (ref "U2") (pin "20") (pinfunction "PF8(SPI5_MISO,SAI1_SCK_B,UART7_RTS,TIM13_CH1,QUADSPI_BK1_IO0,ADC3_IN6)_20") (pintype "bidirectional"))
    )
    (net (code "178") (name "unconnected-(U2F-PF9(SPI5_MOSI,SAI1_FS_B,UART7_CTS,TIM14_CH1,QUADSPI_BK1_IO1,ADC3_IN7)-Pad21)") (class "Default")
      (node (ref "U2") (pin "21") (pinfunction "PF9(SPI5_MOSI,SAI1_FS_B,UART7_CTS,TIM14_CH1,QUADSPI_BK1_IO1,ADC3_IN7)_21") (pintype "bidirectional"))
    )
    (net (code "179") (name "unconnected-(U2F-PF10(QUADSPI_CLK,DCMI_D11,LCD_DE,ADC3_IN8)-Pad22)") (class "Default")
      (node (ref "U2") (pin "22") (pinfunction "PF10(QUADSPI_CLK,DCMI_D11,LCD_DE,ADC3_IN8)_22") (pintype "bidirectional"))
    )
    (net (code "180") (name "unconnected-(U2F-PF11(SPI5_MOSI,SAI2_SD_B,FMC_SDNRAS,DCMI_D12)-Pad49)") (class "Default")
      (node (ref "U2") (pin "49") (pinfunction "PF11(SPI5_MOSI,SAI2_SD_B,FMC_SDNRAS,DCMI_D12)_49") (pintype "bidirectional"))
    )
    (net (code "181") (name "unconnected-(U2F-PF12(FMC_A6)-Pad50)") (class "Default")
      (node (ref "U2") (pin "50") (pinfunction "PF12(FMC_A6)_50") (pintype "bidirectional"))
    )
    (net (code "182") (name "unconnected-(U2F-PF13(I2C4_SMBA,DFSDM1_DATIN6,FMC_A7)-Pad53)") (class "Default")
      (node (ref "U2") (pin "53") (pinfunction "PF13(I2C4_SMBA,DFSDM1_DATIN6,FMC_A7)_53") (pintype "bidirectional"))
    )
    (net (code "183") (name "unconnected-(U2F-PF15(I2C4_SDA,FMC_A9)-Pad55)") (class "Default")
      (node (ref "U2") (pin "55") (pinfunction "PF15(I2C4_SDA,FMC_A9)_55") (pintype "bidirectional"))
    )
    (net (code "184") (name "unconnected-(U2G-PG1(FMC_A11)-Pad57)") (class "Default")
      (node (ref "U2") (pin "57") (pinfunction "PG1(FMC_A11)_57") (pintype "bidirectional"))
    )
    (net (code "185") (name "unconnected-(U2G-PG2(FMC_A12)-Pad87)") (class "Default")
      (node (ref "U2") (pin "87") (pinfunction "PG2(FMC_A12)_87") (pintype "bidirectional"))
    )
    (net (code "186") (name "unconnected-(U2G-PG3(FMC_A13)-Pad88)") (class "Default")
      (node (ref "U2") (pin "88") (pinfunction "PG3(FMC_A13)_88") (pintype "bidirectional"))
    )
    (net (code "187") (name "unconnected-(U2G-PG4(FMC_A14{slash}FMC_BA0)-Pad89)") (class "Default")
      (node (ref "U2") (pin "89") (pinfunction "PG4(FMC_A14/FMC_BA0)_89") (pintype "bidirectional"))
    )
    (net (code "188") (name "unconnected-(U2G-PG5(FMC_A15{slash}FMC_BA1)-Pad90)") (class "Default")
      (node (ref "U2") (pin "90") (pinfunction "PG5(FMC_A15/FMC_BA1)_90") (pintype "bidirectional"))
    )
    (net (code "189") (name "unconnected-(U2G-PG6(FMC_NE3,DCMI_D12,LCD_R7))-Pad91)") (class "Default")
      (node (ref "U2") (pin "91") (pinfunction "PG6(FMC_NE3,DCMI_D12,LCD_R7))_91") (pintype "bidirectional"))
    )
    (net (code "190") (name "unconnected-(U2G-PG7(SAI1_MCLK_A,USART6_CK,FMC_INT,DCMII_D13,LCD_CLK)-Pad92)") (class "Default")
      (node (ref "U2") (pin "92") (pinfunction "PG7(SAI1_MCLK_A,USART6_CK,FMC_INT,DCMII_D13,LCD_CLK)_92") (pintype "bidirectional"))
    )
    (net (code "191") (name "unconnected-(U2G-PG8(SPI6_NSS,SPDIF_RX2,USART6_RTS,ETH_PPS_OUT,FMC_SDCLK,LCD_G7)-Pad93)") (class "Default")
      (node (ref "U2") (pin "93") (pinfunction "PG8(SPI6_NSS,SPDIF_RX2,USART6_RTS,ETH_PPS_OUT,FMC_SDCLK,LCD_G7)_93") (pintype "bidirectional"))
    )
    (net (code "192") (name "unconnected-(U2G-PG10(SPI1_NSS{slash}I2S1_WS,LCD_G3,SAI2_SD_B,SDMMC2_D1,FMC_NE3,DCMI_D2,LCD_B2)-Pad125)") (class "Default")
      (node (ref "U2") (pin "125") (pinfunction "PG10(SPI1_NSS/I2S1_WS,LCD_G3,SAI2_SD_B,SDMMC2_D1,FMC_NE3,DCMI_D2,LCD_B2)_125") (pintype "bidirectional"))
    )
    (net (code "193") (name "unconnected-(U2G-PG11(SPI1_SCK{slash}I2S1_CK,SPDIF_RX0,SDMMC2_D2,ETH_MII_TX_EN{slash}ETH_RMII_TX_EN,DCMI_D3,LCD_B3)-Pad126)") (class "Default")
      (node (ref "U2") (pin "126") (pinfunction "PG11(SPI1_SCK/I2S1_CK,SPDIF_RX0,SDMMC2_D2,ETH_MII_TX_EN/ETH_RMII_TX_EN,DCMI_D3,LCD_B3)_126") (pintype "bidirectional"))
    )
    (net (code "194") (name "unconnected-(U2G-PG12(LPTIM1_IN1,SPI6_MISO,SPDIF_RX1,USART6_RTS,LCD_B4,SDMMC2_D3,FMC_NE4,LCD_B1)-Pad127)") (class "Default")
      (node (ref "U2") (pin "127") (pinfunction "PG12(LPTIM1_IN1,SPI6_MISO,SPDIF_RX1,USART6_RTS,LCD_B4,SDMMC2_D3,FMC_NE4,LCD_B1)_127") (pintype "bidirectional"))
    )
    (net (code "195") (name "unconnected-(U2G-PG13(TRACED0,LPTIM1_OUT,SPI6_SCK,USART6_CTS,ETH_MII_TXD0{slash}ETH_RMII_TXD0,FMC_A24,LCD_R0)-Pad128)") (class "Default")
      (node (ref "U2") (pin "128") (pinfunction "PG13(TRACED0,LPTIM1_OUT,SPI6_SCK,USART6_CTS,ETH_MII_TXD0/ETH_RMII_TXD0,FMC_A24,LCD_R0)_128") (pintype "bidirectional"))
    )
    (net (code "196") (name "unconnected-(U2G-PG14(TRACED1,LPTIM1_ETR,SPI6_MOSI,USART6_TX,QUADSPI_BK2_IO3,ETH_MII_TXD1{slash}ETH_RMII_TXD1,FMC_A25,LCD_B0)-Pad129)") (class "Default")
      (node (ref "U2") (pin "129") (pinfunction "PG14(TRACED1,LPTIM1_ETR,SPI6_MOSI,USART6_TX,QUADSPI_BK2_IO3,ETH_MII_TXD1/ETH_RMII_TXD1,FMC_A25,LCD_B0)_129") (pintype "bidirectional"))
    )
    (net (code "197") (name "unconnected-(U2G-PG15(USART6_CTS,FMC_SDNCAS,DCMI_D13)-Pad132)") (class "Default")
      (node (ref "U2") (pin "132") (pinfunction "PG15(USART6_CTS,FMC_SDNCAS,DCMI_D13)_132") (pintype "bidirectional"))
    )
    (net (code "198") (name "unconnected-(U3-PA0-Pad10)") (class "Default")
      (node (ref "U3") (pin "10") (pinfunction "PA0_10") (pintype "bidirectional"))
    )
    (net (code "199") (name "unconnected-(U3-PA1-Pad11)") (class "Default")
      (node (ref "U3") (pin "11") (pinfunction "PA1_11") (pintype "bidirectional"))
    )
    (net (code "200") (name "unconnected-(U3-PA5-Pad15)") (class "Default")
      (node (ref "U3") (pin "15") (pinfunction "PA5_15") (pintype "bidirectional"))
    )
    (net (code "201") (name "unconnected-(U3-PA6-Pad16)") (class "Default")
      (node (ref "U3") (pin "16") (pinfunction "PA6_16") (pintype "bidirectional"))
    )
    (net (code "202") (name "unconnected-(U3-PA7-Pad17)") (class "Default")
      (node (ref "U3") (pin "17") (pinfunction "PA7_17") (pintype "bidirectional"))
    )
    (net (code "203") (name "unconnected-(U3-PA11-Pad32)") (class "Default")
      (node (ref "U3") (pin "32") (pinfunction "PA11_32") (pintype "bidirectional"))
    )
    (net (code "204") (name "unconnected-(U3-PA12-Pad33)") (class "Default")
      (node (ref "U3") (pin "33") (pinfunction "PA12_33") (pintype "bidirectional"))
    )
    (net (code "205") (name "unconnected-(U3-PA15-Pad38)") (class "Default")
      (node (ref "U3") (pin "38") (pinfunction "PA15_38") (pintype "bidirectional"))
    )
    (net (code "206") (name "unconnected-(U3-PB1-Pad19)") (class "Default")
      (node (ref "U3") (pin "19") (pinfunction "PB1_19") (pintype "bidirectional"))
    )
    (net (code "207") (name "unconnected-(U3-PB3-Pad39)") (class "Default")
      (node (ref "U3") (pin "39") (pinfunction "PB3_39") (pintype "bidirectional"))
    )
    (net (code "208") (name "unconnected-(U3-PB4-Pad40)") (class "Default")
      (node (ref "U3") (pin "40") (pinfunction "PB4_40") (pintype "bidirectional"))
    )
    (net (code "209") (name "unconnected-(U3-PB5-Pad41)") (class "Default")
      (node (ref "U3") (pin "41") (pinfunction "PB5_41") (pintype "bidirectional"))
    )
    (net (code "210") (name "unconnected-(U3-PB8-Pad45)") (class "Default")
      (node (ref "U3") (pin "45") (pinfunction "PB8_45") (pintype "bidirectional"))
    )
    (net (code "211") (name "unconnected-(U3-PB9-Pad46)") (class "Default")
      (node (ref "U3") (pin "46") (pinfunction "PB9_46") (pintype "bidirectional"))
    )
    (net (code "212") (name "unconnected-(U3-PC13-Pad2)") (class "Default")
      (node (ref "U3") (pin "2") (pinfunction "PC13_2") (pintype "bidirectional"))
    )
    (net (code "213") (name "unconnected-(U3-PC14-OSC32_IN-Pad3)") (class "Default")
      (node (ref "U3") (pin "3") (pinfunction "PC14-OSC32_IN_3") (pintype "bidirectional"))
    )
    (net (code "214") (name "unconnected-(U3-PC15-OSC32_OUT-Pad4)") (class "Default")
      (node (ref "U3") (pin "4") (pinfunction "PC15-OSC32_OUT_4") (pintype "bidirectional"))
    )
    (net (code "215") (name "unconnected-(U3-VLCD-Pad1)") (class "Default")
      (node (ref "U3") (pin "1") (pinfunction "VLCD_1") (pintype "bidirectional"))
    )
    (net (code "216") (name "unconnected-(U4-PG-PadP$2)") (class "Default")
      (node (ref "U4") (pin "P$2") (pinfunction "PG_P$2") (pintype "bidirectional"))
    )
  )
)
